# PCB1_v1.net
KiCad netlist of a schematic drawn in EAGLE
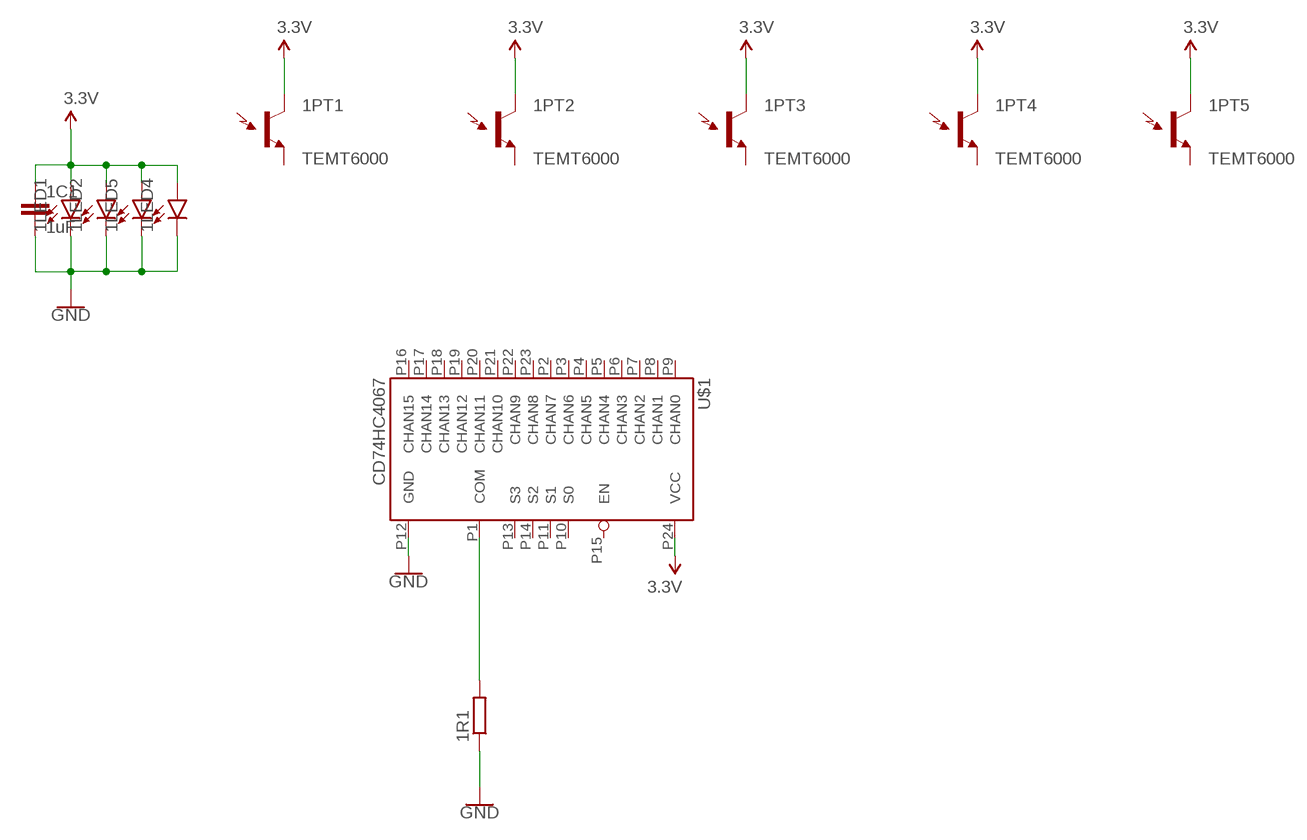
[diagram p0: schematic, sheet 1]
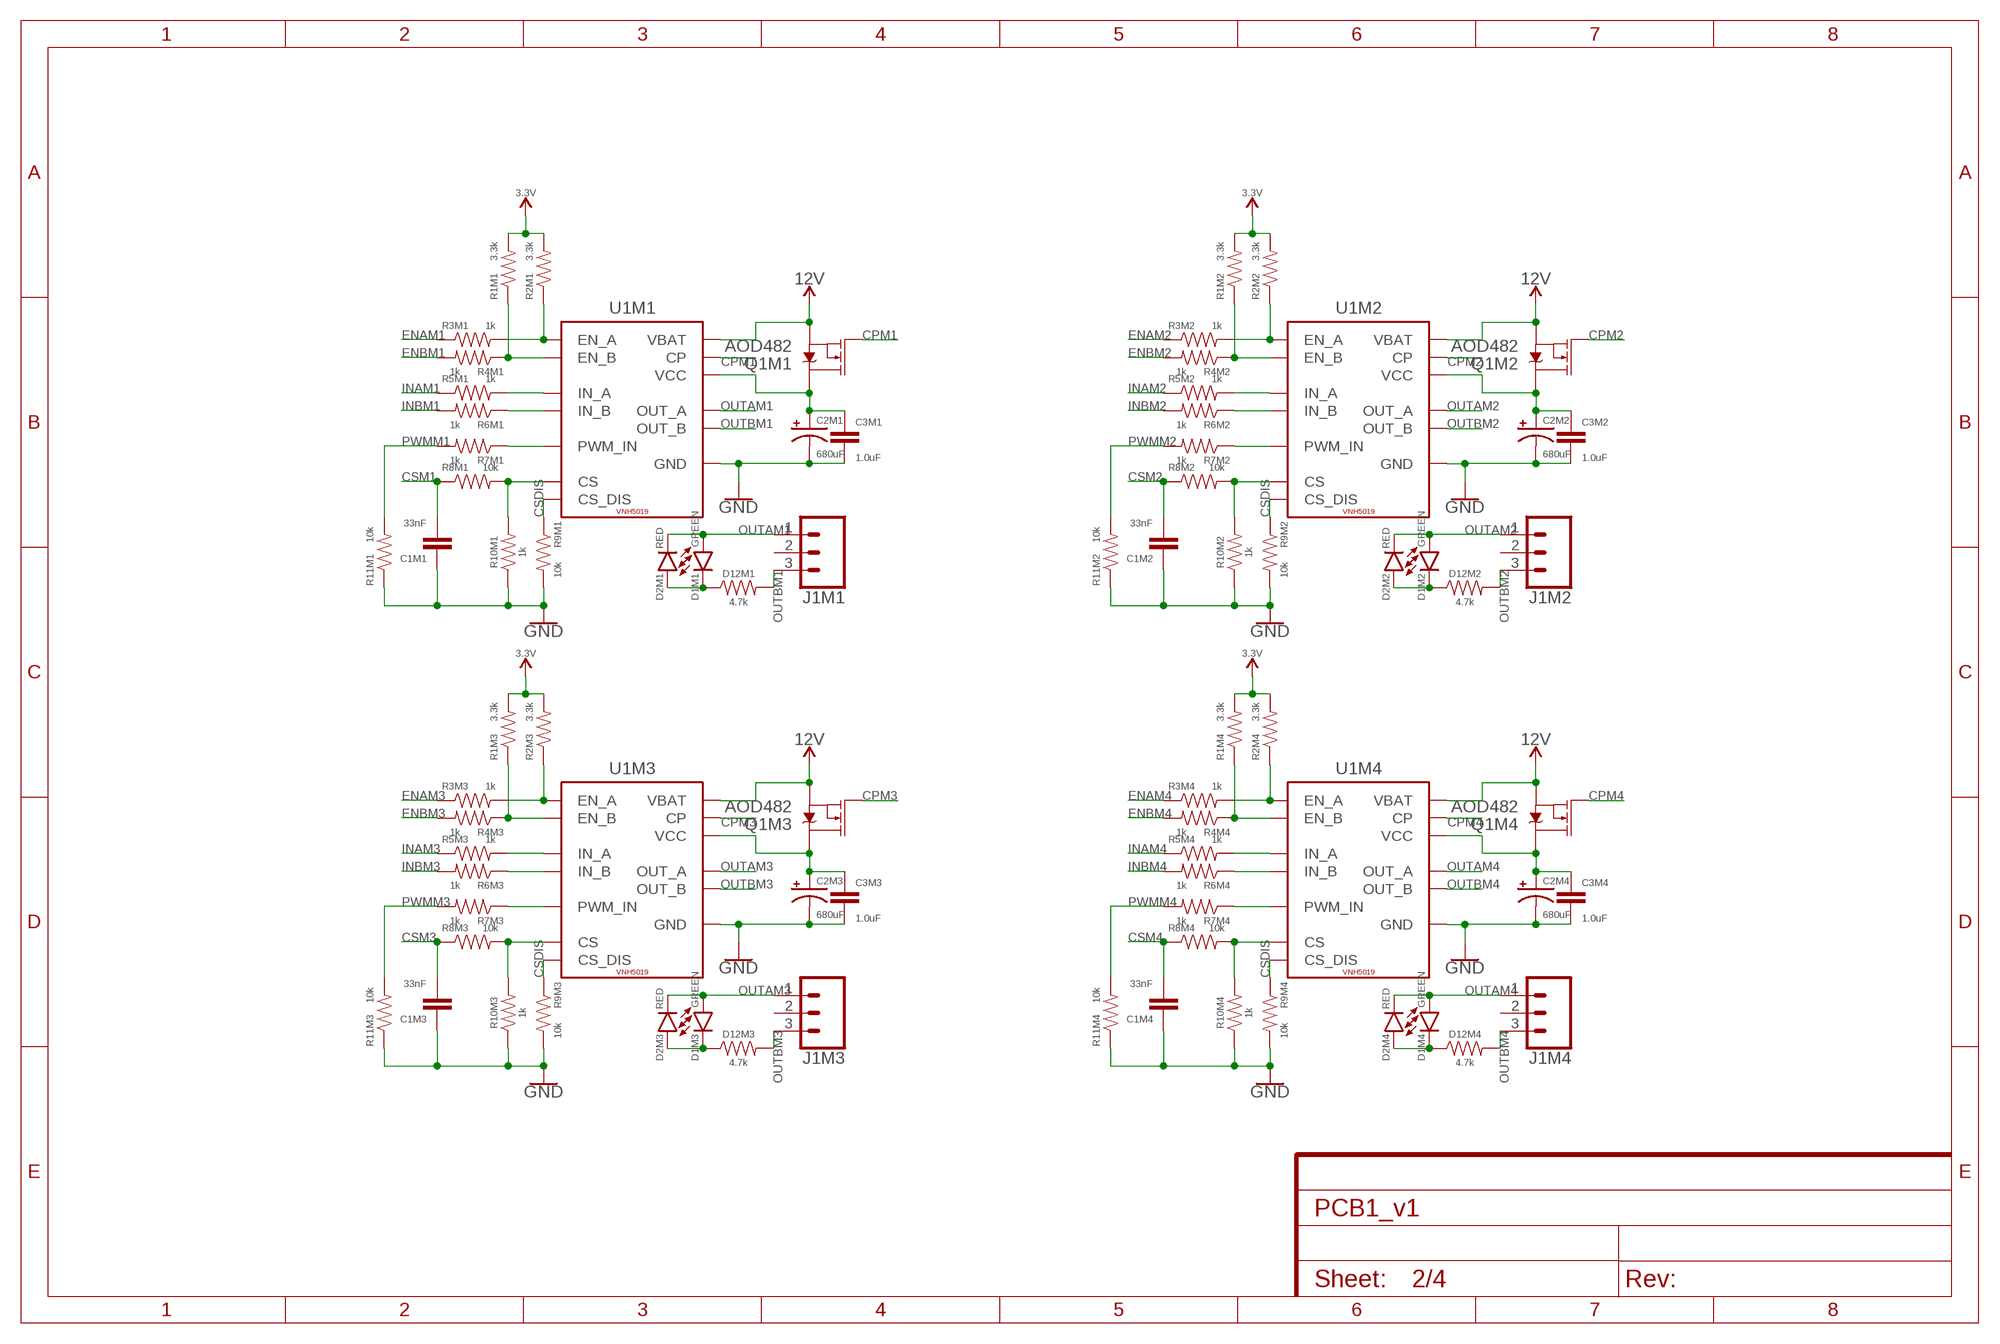
[diagram p1: schematic, sheet 2]
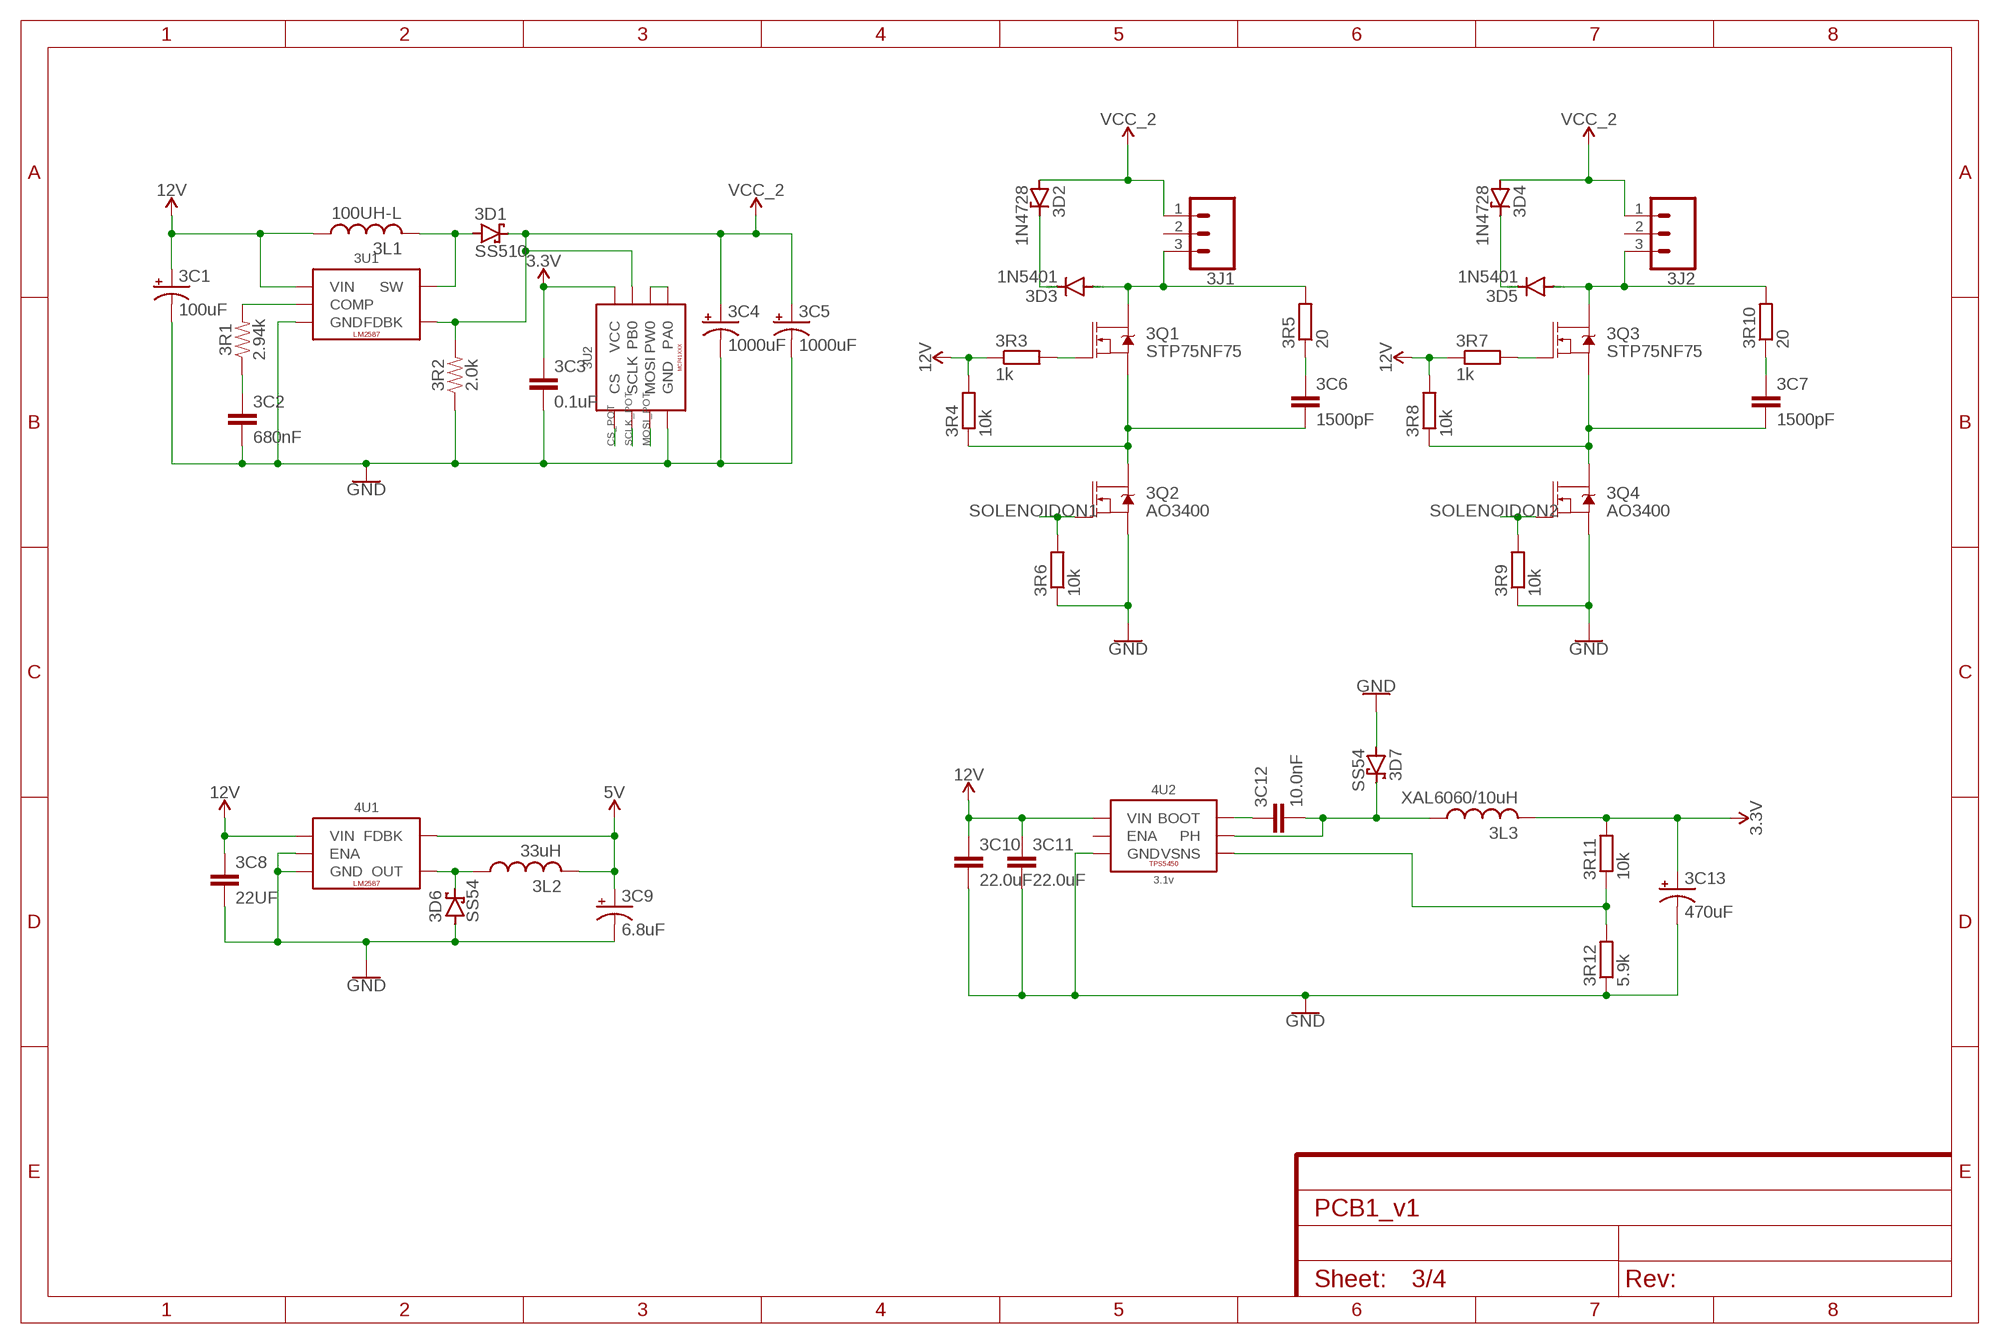
[diagram p2: schematic, sheet 3]
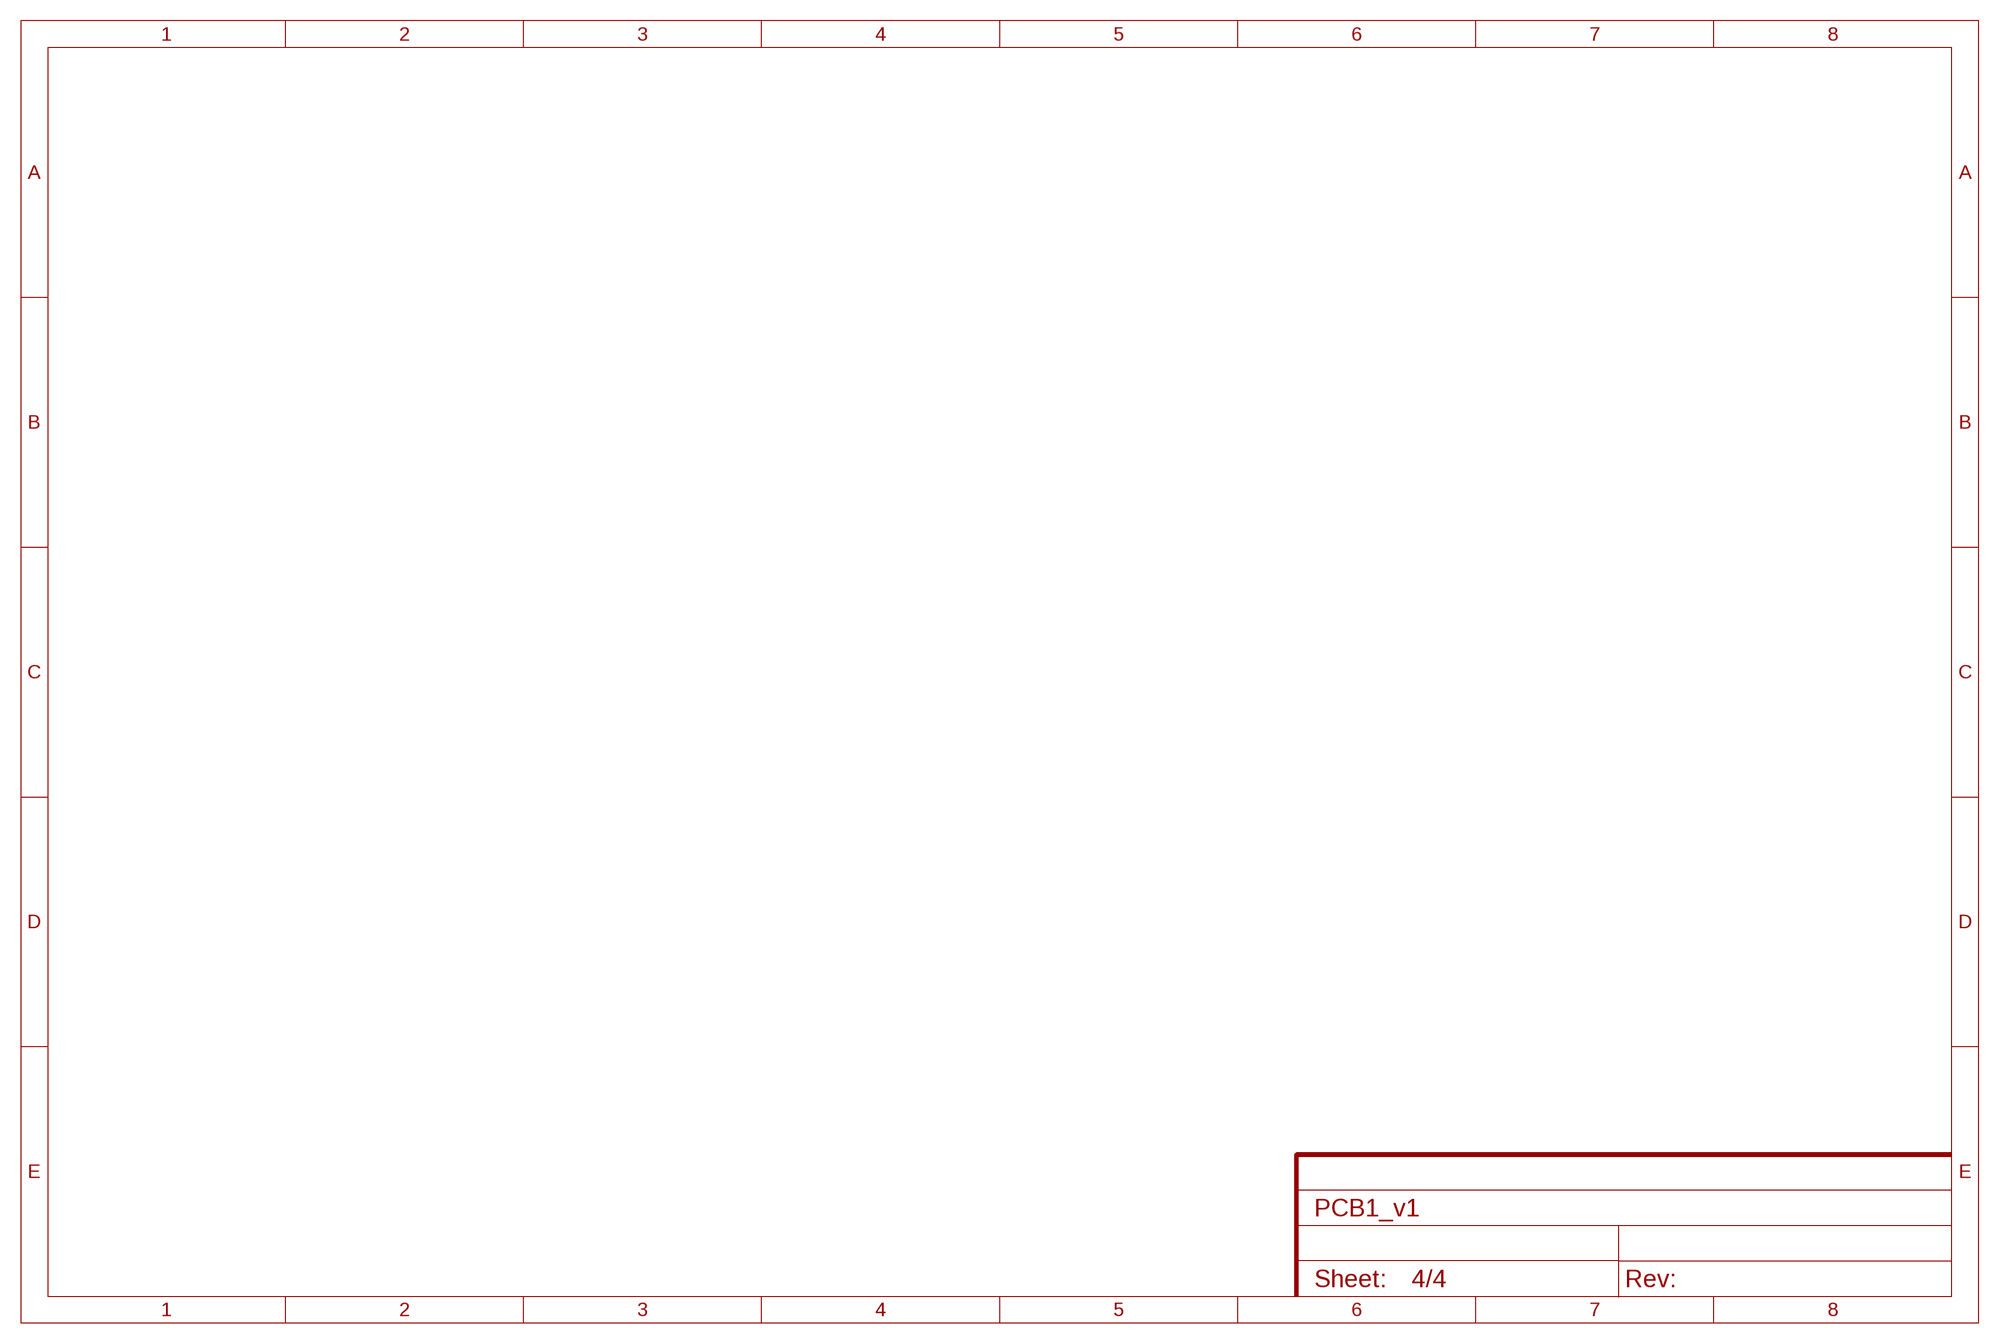
[diagram p3: schematic, sheet 4]

(export (version "E")
  (design (tool "Eeschema 10.0.6"))
  (components
    (comp (ref "3C1")
      (value "100uF")
      (footprint "eagle-import:PANASONIC_D")
      (libsource (lib "eagle-import") (part "100UF-POLAR-25V-20%(ELEC)"))
    )
    (comp (ref "3C2")
      (value "680nF")
      (footprint "eagle-import:0603")
      (libsource (lib "eagle-import") (part "680PF-0603-50V-10%"))
    )
    (comp (ref "3C3")
      (value "0.1uF")
      (footprint "eagle-import:0603")
      (libsource (lib "eagle-import") (part "0.1UF-0603-25V-5%"))
    )
    (comp (ref "3C4")
      (value "1000uF")
      (footprint "eagle-import:1000UF-CAP")
      (libsource (lib "eagle-import") (part "1000UF-CAP"))
    )
    (comp (ref "3C5")
      (value "1000uF")
      (footprint "eagle-import:1000UF-CAP")
      (libsource (lib "eagle-import") (part "1000UF-CAP"))
    )
    (comp (ref "3C6")
      (value "1500pF")
      (footprint "eagle-import:C0603")
      (libsource (lib "eagle-import") (part "C-EUC0603"))
    )
    (comp (ref "3C7")
      (value "1500pF")
      (footprint "eagle-import:C0603")
      (libsource (lib "eagle-import") (part "C-EUC0603"))
    )
    (comp (ref "3C8")
      (value "22UF")
      (footprint "eagle-import:1210")
      (libsource (lib "eagle-import") (part "22UF-1210-16V-20%"))
    )
    (comp (ref "3C9")
      (value "6.8uF")
      (footprint "eagle-import:A_3216-18R")
      (libsource (lib "eagle-import") (part "CPOL-USA/3216-18R"))
    )
    (comp (ref "3C10")
      (value "22.0uF")
      (footprint "eagle-import:C1210")
      (libsource (lib "eagle-import") (part "C-EUC1210"))
    )
    (comp (ref "3C11")
      (value "22.0uF")
      (footprint "eagle-import:C1210")
      (libsource (lib "eagle-import") (part "C-EUC1210"))
    )
    (comp (ref "3C12")
      (value "10.0nF")
      (footprint "eagle-import:C0603")
      (libsource (lib "eagle-import") (part "C-EUC0603"))
    )
    (comp (ref "3C13")
      (value "470uF")
      (footprint "eagle-import:D_7343-31R")
      (libsource (lib "eagle-import") (part "CPOL-USD/7343-31R"))
    )
    (comp (ref "3D1")
      (value "SS510")
      (footprint "eagle-import:SMB")
      (libsource (lib "eagle-import") (part "SCHOTTKY-DIODESMD"))
    )
    (comp (ref "3D2")
      (value "1N4728")
      (footprint "eagle-import:DO41Z10")
      (libsource (lib "eagle-import") (part "1N4728"))
    )
    (comp (ref "3D3")
      (value "1N5401")
      (footprint "eagle-import:DO201-15")
      (libsource (lib "eagle-import") (part "1N5400"))
    )
    (comp (ref "3D4")
      (value "1N4728")
      (footprint "eagle-import:DO41Z10")
      (libsource (lib "eagle-import") (part "1N4728"))
    )
    (comp (ref "3D5")
      (value "1N5401")
      (footprint "eagle-import:DO201-15")
      (libsource (lib "eagle-import") (part "1N5400"))
    )
    (comp (ref "3D6")
      (value "SS54")
      (footprint "eagle-import:SMB")
      (libsource (lib "eagle-import") (part "SCHOTTKY-DIODESMD"))
    )
    (comp (ref "3D7")
      (value "SS54")
      (footprint "eagle-import:SMB")
      (libsource (lib "eagle-import") (part "SCHOTTKY-DIODESMD"))
    )
    (comp (ref "3J1")
      (value "CONN_03-SCREW-5MM")
      (footprint "eagle-import:SCREWTERMINAL-5MM-3")
      (libsource (lib "eagle-import") (part "CONN_03-SCREW-5MM"))
    )
    (comp (ref "3J2")
      (value "CONN_03-SCREW-5MM")
      (footprint "eagle-import:SCREWTERMINAL-5MM-3")
      (libsource (lib "eagle-import") (part "CONN_03-SCREW-5MM"))
    )
    (comp (ref "3L1")
      (value "100UH-L")
      (footprint "eagle-import:100UH-L")
      (libsource (lib "eagle-import") (part "100UH-L"))
    )
    (comp (ref "3L2")
      (value "33uH")
      (footprint "eagle-import:127")
      (libsource (lib "eagle-import") (part "CDRH127"))
    )
    (comp (ref "3L3")
      (value "XAL6060/10uH")
      (footprint "eagle-import:XAL6060")
      (libsource (lib "eagle-import") (part "XAL6060"))
    )
    (comp (ref "3Q1")
      (value "STP75NF75")
      (footprint "eagle-import:TO220V")
      (libsource (lib "eagle-import") (part "MOSFET-NCH-FQP30N06L"))
    )
    (comp (ref "3Q2")
      (value "AO3400")
      (footprint "eagle-import:SOT23-3")
      (libsource (lib "eagle-import") (part "MOSFET-NCH-AO3404A"))
    )
    (comp (ref "3Q3")
      (value "STP75NF75")
      (footprint "eagle-import:TO220V")
      (libsource (lib "eagle-import") (part "MOSFET-NCH-FQP30N06L"))
    )
    (comp (ref "3Q4")
      (value "AO3400")
      (footprint "eagle-import:SOT23-3")
      (libsource (lib "eagle-import") (part "MOSFET-NCH-AO3404A"))
    )
    (comp (ref "3R1")
      (value "2.94k")
      (footprint "eagle-import:0603")
      (libsource (lib "eagle-import") (part "RESISTOR0603"))
    )
    (comp (ref "3R2")
      (value "2.0k")
      (footprint "eagle-import:0603")
      (libsource (lib "eagle-import") (part "2.0KOHM-0603-1/10W-5%"))
    )
    (comp (ref "3R3")
      (value "1k")
      (footprint "eagle-import:R0603")
      (libsource (lib "eagle-import") (part "R-EU_R0603"))
    )
    (comp (ref "3R4")
      (value "10k")
      (footprint "eagle-import:R0603")
      (libsource (lib "eagle-import") (part "R-EU_R0603"))
    )
    (comp (ref "3R5")
      (value "20")
      (footprint "eagle-import:R0603")
      (libsource (lib "eagle-import") (part "R-EU_R0603"))
    )
    (comp (ref "3R6")
      (value "10k")
      (footprint "eagle-import:R0603")
      (libsource (lib "eagle-import") (part "R-EU_R0603"))
    )
    (comp (ref "3R7")
      (value "1k")
      (footprint "eagle-import:R0603")
      (libsource (lib "eagle-import") (part "R-EU_R0603"))
    )
    (comp (ref "3R8")
      (value "10k")
      (footprint "eagle-import:R0603")
      (libsource (lib "eagle-import") (part "R-EU_R0603"))
    )
    (comp (ref "3R9")
      (value "10k")
      (footprint "eagle-import:R0603")
      (libsource (lib "eagle-import") (part "R-EU_R0603"))
    )
    (comp (ref "3R10")
      (value "20")
      (footprint "eagle-import:R0603")
      (libsource (lib "eagle-import") (part "R-EU_R0603"))
    )
    (comp (ref "3R11")
      (value "10k")
      (footprint "eagle-import:R0603")
      (libsource (lib "eagle-import") (part "R-EU_R0603"))
    )
    (comp (ref "3R12")
      (value "5.9k")
      (footprint "eagle-import:R0603")
      (libsource (lib "eagle-import") (part "R-EU_R0603"))
    )
    (comp (ref "3U1")
      (value "LM2587")
      (footprint "eagle-import:TO-263")
      (libsource (lib "eagle-import") (part "LM2587"))
    )
    (comp (ref "3U2")
      (value "MCP41XXX")
      (footprint "eagle-import:SOIC-8")
      (libsource (lib "eagle-import") (part "MCP41XXX"))
    )
    (comp (ref "4U1")
      (value "LM2596")
      (footprint "eagle-import:TO-263")
      (libsource (lib "eagle-import") (part "LM2596"))
    )
    (comp (ref "4U2")
      (value "3.1v")
      (footprint "eagle-import:POWERPAD-SOIC-8")
      (libsource (lib "eagle-import") (part "TPS5450"))
    )
    (comp (ref "1C1")
      (value "1uF")
      (footprint "eagle-import:C0603")
      (libsource (lib "eagle-import") (part "C-EUC0603"))
    )
    (comp (ref "1LED1")
      (value "3528LED")
      (footprint "eagle-import:3528")
      (libsource (lib "eagle-import") (part "3528LED"))
    )
    (comp (ref "1LED2")
      (value "3528LED")
      (footprint "eagle-import:3528")
      (libsource (lib "eagle-import") (part "3528LED"))
    )
    (comp (ref "1LED4")
      (value "3528LED")
      (footprint "eagle-import:3528")
      (libsource (lib "eagle-import") (part "3528LED"))
    )
    (comp (ref "1LED5")
      (value "3528LED")
      (footprint "eagle-import:3528")
      (libsource (lib "eagle-import") (part "3528LED"))
    )
    (comp (ref "1PT1")
      (value "TEMT6000")
      (footprint "eagle-import:TEMT6000")
      (libsource (lib "eagle-import") (part "LIGHT_SENSORTEMT6000"))
    )
    (comp (ref "1PT2")
      (value "TEMT6000")
      (footprint "eagle-import:TEMT6000")
      (libsource (lib "eagle-import") (part "LIGHT_SENSORTEMT6000"))
    )
    (comp (ref "1PT3")
      (value "TEMT6000")
      (footprint "eagle-import:TEMT6000")
      (libsource (lib "eagle-import") (part "LIGHT_SENSORTEMT6000"))
    )
    (comp (ref "1PT4")
      (value "TEMT6000")
      (footprint "eagle-import:TEMT6000")
      (libsource (lib "eagle-import") (part "LIGHT_SENSORTEMT6000"))
    )
    (comp (ref "1PT5")
      (value "TEMT6000")
      (footprint "eagle-import:TEMT6000")
      (libsource (lib "eagle-import") (part "LIGHT_SENSORTEMT6000"))
    )
    (comp (ref "1R1")
      (value "2k")
      (footprint "eagle-import:R0603")
      (libsource (lib "eagle-import") (part "R-EU_R0603"))
    )
    (comp (ref "U$1")
      (value "CD74HC4067")
      (footprint "eagle-import:SOIC-24")
      (libsource (lib "eagle-import") (part "CD74HC4067"))
    )
    (comp (ref "C1M1")
      (value "33nF")
      (footprint "eagle-import:0603")
      (libsource (lib "eagle-import") (part "33NF-0603-50V-10%"))
    )
    (comp (ref "C1M2")
      (value "33nF")
      (footprint "eagle-import:0603")
      (libsource (lib "eagle-import") (part "33NF-0603-50V-10%"))
    )
    (comp (ref "C1M3")
      (value "33nF")
      (footprint "eagle-import:0603")
      (libsource (lib "eagle-import") (part "33NF-0603-50V-10%"))
    )
    (comp (ref "C1M4")
      (value "33nF")
      (footprint "eagle-import:0603")
      (libsource (lib "eagle-import") (part "33NF-0603-50V-10%"))
    )
    (comp (ref "C2M1")
      (value "680uF")
      (footprint "eagle-import:E3,5-8")
      (libsource (lib "eagle-import") (part "CPOL-USE3.5-8"))
    )
    (comp (ref "C2M2")
      (value "680uF")
      (footprint "eagle-import:E3,5-8")
      (libsource (lib "eagle-import") (part "CPOL-USE3.5-8"))
    )
    (comp (ref "C2M3")
      (value "680uF")
      (footprint "eagle-import:E3,5-8")
      (libsource (lib "eagle-import") (part "CPOL-USE3.5-8"))
    )
    (comp (ref "C2M4")
      (value "680uF")
      (footprint "eagle-import:E3,5-8")
      (libsource (lib "eagle-import") (part "CPOL-USE3.5-8"))
    )
    (comp (ref "C3M1")
      (value "1.0uF")
      (footprint "eagle-import:0603")
      (libsource (lib "eagle-import") (part "1.0UF-0603-16V-10%-X7R"))
    )
    (comp (ref "C3M2")
      (value "1.0uF")
      (footprint "eagle-import:0603")
      (libsource (lib "eagle-import") (part "1.0UF-0603-16V-10%-X7R"))
    )
    (comp (ref "C3M3")
      (value "1.0uF")
      (footprint "eagle-import:0603")
      (libsource (lib "eagle-import") (part "1.0UF-0603-16V-10%-X7R"))
    )
    (comp (ref "C3M4")
      (value "1.0uF")
      (footprint "eagle-import:0603")
      (libsource (lib "eagle-import") (part "1.0UF-0603-16V-10%-X7R"))
    )
    (comp (ref "D1M1")
      (value "GREEN")
      (footprint "eagle-import:LED-1206")
      (libsource (lib "eagle-import") (part "LED-GREEN1206"))
    )
    (comp (ref "D1M2")
      (value "GREEN")
      (footprint "eagle-import:LED-1206")
      (libsource (lib "eagle-import") (part "LED-GREEN1206"))
    )
    (comp (ref "D1M3")
      (value "GREEN")
      (footprint "eagle-import:LED-1206")
      (libsource (lib "eagle-import") (part "LED-GREEN1206"))
    )
    (comp (ref "D1M4")
      (value "GREEN")
      (footprint "eagle-import:LED-1206")
      (libsource (lib "eagle-import") (part "LED-GREEN1206"))
    )
    (comp (ref "D2M1")
      (value "RED")
      (footprint "eagle-import:LED-1206")
      (libsource (lib "eagle-import") (part "LED-RED1206"))
    )
    (comp (ref "D2M2")
      (value "RED")
      (footprint "eagle-import:LED-1206")
      (libsource (lib "eagle-import") (part "LED-RED1206"))
    )
    (comp (ref "D2M3")
      (value "RED")
      (footprint "eagle-import:LED-1206")
      (libsource (lib "eagle-import") (part "LED-RED1206"))
    )
    (comp (ref "D2M4")
      (value "RED")
      (footprint "eagle-import:LED-1206")
      (libsource (lib "eagle-import") (part "LED-RED1206"))
    )
    (comp (ref "D12M1")
      (value "4.7k")
      (footprint "eagle-import:0603")
      (libsource (lib "eagle-import") (part "4.7KOHM-0603-1/10W-1%"))
    )
    (comp (ref "D12M2")
      (value "4.7k")
      (footprint "eagle-import:0603")
      (libsource (lib "eagle-import") (part "4.7KOHM-0603-1/10W-1%"))
    )
    (comp (ref "D12M3")
      (value "4.7k")
      (footprint "eagle-import:0603")
      (libsource (lib "eagle-import") (part "4.7KOHM-0603-1/10W-1%"))
    )
    (comp (ref "D12M4")
      (value "4.7k")
      (footprint "eagle-import:0603")
      (libsource (lib "eagle-import") (part "4.7KOHM-0603-1/10W-1%"))
    )
    (comp (ref "J1M1")
      (value "CONN_03-SCREW-5MM")
      (footprint "eagle-import:SCREWTERMINAL-5MM-3")
      (libsource (lib "eagle-import") (part "CONN_03-SCREW-5MM"))
    )
    (comp (ref "J1M2")
      (value "CONN_03-SCREW-5MM")
      (footprint "eagle-import:SCREWTERMINAL-5MM-3")
      (libsource (lib "eagle-import") (part "CONN_03-SCREW-5MM"))
    )
    (comp (ref "J1M3")
      (value "CONN_03-SCREW-5MM")
      (footprint "eagle-import:SCREWTERMINAL-5MM-3")
      (libsource (lib "eagle-import") (part "CONN_03-SCREW-5MM"))
    )
    (comp (ref "J1M4")
      (value "CONN_03-SCREW-5MM")
      (footprint "eagle-import:SCREWTERMINAL-5MM-3")
      (libsource (lib "eagle-import") (part "CONN_03-SCREW-5MM"))
    )
    (comp (ref "Q1M1")
      (value "AOD482")
      (footprint "eagle-import:DPAK")
      (libsource (lib "eagle-import") (part "MOSFET-NCH-FDD8780"))
    )
    (comp (ref "Q1M2")
      (value "AOD482")
      (footprint "eagle-import:DPAK")
      (libsource (lib "eagle-import") (part "MOSFET-NCH-FDD8780"))
    )
    (comp (ref "Q1M3")
      (value "AOD482")
      (footprint "eagle-import:DPAK")
      (libsource (lib "eagle-import") (part "MOSFET-NCH-FDD8780"))
    )
    (comp (ref "Q1M4")
      (value "AOD482")
      (footprint "eagle-import:DPAK")
      (libsource (lib "eagle-import") (part "MOSFET-NCH-FDD8780"))
    )
    (comp (ref "R1M1")
      (value "3.3k")
      (footprint "eagle-import:0603")
      (libsource (lib "eagle-import") (part "3.3KOHM-0603-1/10W-1%"))
    )
    (comp (ref "R1M2")
      (value "3.3k")
      (footprint "eagle-import:0603")
      (libsource (lib "eagle-import") (part "3.3KOHM-0603-1/10W-1%"))
    )
    (comp (ref "R1M3")
      (value "3.3k")
      (footprint "eagle-import:0603")
      (libsource (lib "eagle-import") (part "3.3KOHM-0603-1/10W-1%"))
    )
    (comp (ref "R1M4")
      (value "3.3k")
      (footprint "eagle-import:0603")
      (libsource (lib "eagle-import") (part "3.3KOHM-0603-1/10W-1%"))
    )
    (comp (ref "R2M1")
      (value "3.3k")
      (footprint "eagle-import:0603")
      (libsource (lib "eagle-import") (part "3.3KOHM-0603-1/10W-1%"))
    )
    (comp (ref "R2M2")
      (value "3.3k")
      (footprint "eagle-import:0603")
      (libsource (lib "eagle-import") (part "3.3KOHM-0603-1/10W-1%"))
    )
    (comp (ref "R2M3")
      (value "3.3k")
      (footprint "eagle-import:0603")
      (libsource (lib "eagle-import") (part "3.3KOHM-0603-1/10W-1%"))
    )
    (comp (ref "R2M4")
      (value "3.3k")
      (footprint "eagle-import:0603")
      (libsource (lib "eagle-import") (part "3.3KOHM-0603-1/10W-1%"))
    )
    (comp (ref "R3M1")
      (value "1k")
      (footprint "eagle-import:0603")
      (libsource (lib "eagle-import") (part "1KOHM-0603-1/10W-1%"))
    )
    (comp (ref "R3M2")
      (value "1k")
      (footprint "eagle-import:0603")
      (libsource (lib "eagle-import") (part "1KOHM-0603-1/10W-1%"))
    )
    (comp (ref "R3M3")
      (value "1k")
      (footprint "eagle-import:0603")
      (libsource (lib "eagle-import") (part "1KOHM-0603-1/10W-1%"))
    )
    (comp (ref "R3M4")
      (value "1k")
      (footprint "eagle-import:0603")
      (libsource (lib "eagle-import") (part "1KOHM-0603-1/10W-1%"))
    )
    (comp (ref "R4M1")
      (value "1k")
      (footprint "eagle-import:0603")
      (libsource (lib "eagle-import") (part "1KOHM-0603-1/10W-1%"))
    )
    (comp (ref "R4M2")
      (value "1k")
      (footprint "eagle-import:0603")
      (libsource (lib "eagle-import") (part "1KOHM-0603-1/10W-1%"))
    )
    (comp (ref "R4M3")
      (value "1k")
      (footprint "eagle-import:0603")
      (libsource (lib "eagle-import") (part "1KOHM-0603-1/10W-1%"))
    )
    (comp (ref "R4M4")
      (value "1k")
      (footprint "eagle-import:0603")
      (libsource (lib "eagle-import") (part "1KOHM-0603-1/10W-1%"))
    )
    (comp (ref "R5M1")
      (value "1k")
      (footprint "eagle-import:0603")
      (libsource (lib "eagle-import") (part "1KOHM-0603-1/10W-1%"))
    )
    (comp (ref "R5M2")
      (value "1k")
      (footprint "eagle-import:0603")
      (libsource (lib "eagle-import") (part "1KOHM-0603-1/10W-1%"))
    )
    (comp (ref "R5M3")
      (value "1k")
      (footprint "eagle-import:0603")
      (libsource (lib "eagle-import") (part "1KOHM-0603-1/10W-1%"))
    )
    (comp (ref "R5M4")
      (value "1k")
      (footprint "eagle-import:0603")
      (libsource (lib "eagle-import") (part "1KOHM-0603-1/10W-1%"))
    )
    (comp (ref "R6M1")
      (value "1k")
      (footprint "eagle-import:0603")
      (libsource (lib "eagle-import") (part "1KOHM-0603-1/10W-1%"))
    )
    (comp (ref "R6M2")
      (value "1k")
      (footprint "eagle-import:0603")
      (libsource (lib "eagle-import") (part "1KOHM-0603-1/10W-1%"))
    )
    (comp (ref "R6M3")
      (value "1k")
      (footprint "eagle-import:0603")
      (libsource (lib "eagle-import") (part "1KOHM-0603-1/10W-1%"))
    )
    (comp (ref "R6M4")
      (value "1k")
      (footprint "eagle-import:0603")
      (libsource (lib "eagle-import") (part "1KOHM-0603-1/10W-1%"))
    )
    (comp (ref "R7M1")
      (value "1k")
      (footprint "eagle-import:0603")
      (libsource (lib "eagle-import") (part "1KOHM-0603-1/10W-1%"))
    )
    (comp (ref "R7M2")
      (value "1k")
      (footprint "eagle-import:0603")
      (libsource (lib "eagle-import") (part "1KOHM-0603-1/10W-1%"))
    )
    (comp (ref "R7M3")
      (value "1k")
      (footprint "eagle-import:0603")
      (libsource (lib "eagle-import") (part "1KOHM-0603-1/10W-1%"))
    )
    (comp (ref "R7M4")
      (value "1k")
      (footprint "eagle-import:0603")
      (libsource (lib "eagle-import") (part "1KOHM-0603-1/10W-1%"))
    )
    (comp (ref "R8M1")
      (value "10k")
      (footprint "eagle-import:0603")
      (libsource (lib "eagle-import") (part "10KOHM-0603-1/10W-1%"))
    )
    (comp (ref "R8M2")
      (value "10k")
      (footprint "eagle-import:0603")
      (libsource (lib "eagle-import") (part "10KOHM-0603-1/10W-1%"))
    )
    (comp (ref "R8M3")
      (value "10k")
      (footprint "eagle-import:0603")
      (libsource (lib "eagle-import") (part "10KOHM-0603-1/10W-1%"))
    )
    (comp (ref "R8M4")
      (value "10k")
      (footprint "eagle-import:0603")
      (libsource (lib "eagle-import") (part "10KOHM-0603-1/10W-1%"))
    )
    (comp (ref "R9M1")
      (value "10k")
      (footprint "eagle-import:0603")
      (libsource (lib "eagle-import") (part "10KOHM-0603-1/10W-1%"))
    )
    (comp (ref "R9M2")
      (value "10k")
      (footprint "eagle-import:0603")
      (libsource (lib "eagle-import") (part "10KOHM-0603-1/10W-1%"))
    )
    (comp (ref "R9M3")
      (value "10k")
      (footprint "eagle-import:0603")
      (libsource (lib "eagle-import") (part "10KOHM-0603-1/10W-1%"))
    )
    (comp (ref "R9M4")
      (value "10k")
      (footprint "eagle-import:0603")
      (libsource (lib "eagle-import") (part "10KOHM-0603-1/10W-1%"))
    )
    (comp (ref "R10M1")
      (value "1k")
      (footprint "eagle-import:0603")
      (libsource (lib "eagle-import") (part "1KOHM-0603-1/10W-1%"))
    )
    (comp (ref "R10M2")
      (value "1k")
      (footprint "eagle-import:0603")
      (libsource (lib "eagle-import") (part "1KOHM-0603-1/10W-1%"))
    )
    (comp (ref "R10M3")
      (value "1k")
      (footprint "eagle-import:0603")
      (libsource (lib "eagle-import") (part "1KOHM-0603-1/10W-1%"))
    )
    (comp (ref "R10M4")
      (value "1k")
      (footprint "eagle-import:0603")
      (libsource (lib "eagle-import") (part "1KOHM-0603-1/10W-1%"))
    )
    (comp (ref "R11M1")
      (value "10k")
      (footprint "eagle-import:0603")
      (libsource (lib "eagle-import") (part "10KOHM-0603-1/10W-1%"))
    )
    (comp (ref "R11M2")
      (value "10k")
      (footprint "eagle-import:0603")
      (libsource (lib "eagle-import") (part "10KOHM-0603-1/10W-1%"))
    )
    (comp (ref "R11M3")
      (value "10k")
      (footprint "eagle-import:0603")
      (libsource (lib "eagle-import") (part "10KOHM-0603-1/10W-1%"))
    )
    (comp (ref "R11M4")
      (value "10k")
      (footprint "eagle-import:0603")
      (libsource (lib "eagle-import") (part "10KOHM-0603-1/10W-1%"))
    )
    (comp (ref "U1M1")
      (value "VNH5019")
      (footprint "eagle-import:POWERSO-30")
      (libsource (lib "eagle-import") (part "VNH5019"))
    )
    (comp (ref "U1M2")
      (value "VNH5019")
      (footprint "eagle-import:POWERSO-30")
      (libsource (lib "eagle-import") (part "VNH5019"))
    )
    (comp (ref "U1M3")
      (value "VNH5019")
      (footprint "eagle-import:POWERSO-30")
      (libsource (lib "eagle-import") (part "VNH5019"))
    )
    (comp (ref "U1M4")
      (value "VNH5019")
      (footprint "eagle-import:POWERSO-30")
      (libsource (lib "eagle-import") (part "VNH5019"))
    )
  )
  (nets
    (net (code "1") (name "3.3V") (class "Default")
      (node (ref "1C1") (pin "1") (pinfunction "1_1") (pintype "passive"))
      (node (ref "1LED1") (pin "A") (pinfunction "A_A") (pintype "passive"))
      (node (ref "1LED2") (pin "A") (pinfunction "A_A") (pintype "passive"))
      (node (ref "1LED4") (pin "A") (pinfunction "A_A") (pintype "passive"))
      (node (ref "1LED5") (pin "A") (pinfunction "A_A") (pintype "passive"))
      (node (ref "1PT1") (pin "COLLECTOR") (pinfunction "C1_COLLECTOR") (pintype "passive"))
      (node (ref "1PT2") (pin "COLLECTOR") (pinfunction "C1_COLLECTOR") (pintype "passive"))
      (node (ref "1PT3") (pin "COLLECTOR") (pinfunction "C1_COLLECTOR") (pintype "passive"))
      (node (ref "1PT4") (pin "COLLECTOR") (pinfunction "C1_COLLECTOR") (pintype "passive"))
      (node (ref "1PT5") (pin "COLLECTOR") (pinfunction "C1_COLLECTOR") (pintype "passive"))
      (node (ref "3C13") (pin "+") (pinfunction "+_+") (pintype "passive"))
      (node (ref "3C3") (pin "1") (pinfunction "1_1") (pintype "passive"))
      (node (ref "3L3") (pin "2") (pinfunction "2_2") (pintype "passive"))
      (node (ref "3R11") (pin "2") (pinfunction "2_2") (pintype "passive"))
      (node (ref "3U2") (pin "8") (pinfunction "VCC_8") (pintype "power_in"))
      (node (ref "R1M1") (pin "2") (pinfunction "2_2") (pintype "passive"))
      (node (ref "R1M2") (pin "2") (pinfunction "2_2") (pintype "passive"))
      (node (ref "R1M3") (pin "2") (pinfunction "2_2") (pintype "passive"))
      (node (ref "R1M4") (pin "2") (pinfunction "2_2") (pintype "passive"))
      (node (ref "R2M1") (pin "2") (pinfunction "2_2") (pintype "passive"))
      (node (ref "R2M2") (pin "2") (pinfunction "2_2") (pintype "passive"))
      (node (ref "R2M3") (pin "2") (pinfunction "2_2") (pintype "passive"))
      (node (ref "R2M4") (pin "2") (pinfunction "2_2") (pintype "passive"))
      (node (ref "U$1") (pin "P24") (pinfunction "VCC_P24") (pintype "bidirectional"))
    )
    (net (code "2") (name "5V") (class "Default")
      (node (ref "3C9") (pin "+") (pinfunction "+_+") (pintype "passive"))
      (node (ref "3L2") (pin "2") (pinfunction "2_2") (pintype "passive"))
      (node (ref "4U1") (pin "P4") (pinfunction "FDBK_P4") (pintype "output"))
    )
    (net (code "3") (name "12V") (class "Default")
      (node (ref "3C1") (pin "+") (pinfunction "+_+") (pintype "passive"))
      (node (ref "3C10") (pin "1") (pinfunction "1_1") (pintype "passive"))
      (node (ref "3C11") (pin "1") (pinfunction "1_1") (pintype "passive"))
      (node (ref "3C8") (pin "1") (pinfunction "1_1") (pintype "passive"))
      (node (ref "3L1") (pin "P1") (pinfunction "1_P1") (pintype "passive"))
      (node (ref "3R3") (pin "1") (pinfunction "1_1") (pintype "passive"))
      (node (ref "3R4") (pin "2") (pinfunction "2_2") (pintype "passive"))
      (node (ref "3R7") (pin "1") (pinfunction "1_1") (pintype "passive"))
      (node (ref "3R8") (pin "2") (pinfunction "2_2") (pintype "passive"))
      (node (ref "3U1") (pin "P5") (pinfunction "VIN_P5") (pintype "power_in"))
      (node (ref "4U1") (pin "P1") (pinfunction "VIN_P1") (pintype "power_in"))
      (node (ref "4U2") (pin "7") (pinfunction "VIN_7") (pintype "power_in"))
      (node (ref "Q1M1") (pin "3") (pinfunction "S_3") (pintype "bidirectional"))
      (node (ref "Q1M2") (pin "3") (pinfunction "S_3") (pintype "bidirectional"))
      (node (ref "Q1M3") (pin "3") (pinfunction "S_3") (pintype "bidirectional"))
      (node (ref "Q1M4") (pin "3") (pinfunction "S_3") (pintype "bidirectional"))
      (node (ref "U1M1") (pin "P12") (pinfunction "VBAT_P12") (pintype "power_in"))
      (node (ref "U1M2") (pin "P12") (pinfunction "VBAT_P12") (pintype "power_in"))
      (node (ref "U1M3") (pin "P12") (pinfunction "VBAT_P12") (pintype "power_in"))
      (node (ref "U1M4") (pin "P12") (pinfunction "VBAT_P12") (pintype "power_in"))
    )
    (net (code "4") (name "CPM1") (class "Default")
      (node (ref "Q1M1") (pin "1") (pinfunction "G_1") (pintype "bidirectional"))
      (node (ref "U1M1") (pin "P11") (pinfunction "CP_P11") (pintype "output"))
    )
    (net (code "5") (name "CPM2") (class "Default")
      (node (ref "Q1M2") (pin "1") (pinfunction "G_1") (pintype "bidirectional"))
      (node (ref "U1M2") (pin "P11") (pinfunction "CP_P11") (pintype "output"))
    )
    (net (code "6") (name "CPM3") (class "Default")
      (node (ref "Q1M3") (pin "1") (pinfunction "G_1") (pintype "bidirectional"))
      (node (ref "U1M3") (pin "P11") (pinfunction "CP_P11") (pintype "output"))
    )
    (net (code "7") (name "CPM4") (class "Default")
      (node (ref "Q1M4") (pin "1") (pinfunction "G_1") (pintype "bidirectional"))
      (node (ref "U1M4") (pin "P11") (pinfunction "CP_P11") (pintype "output"))
    )
    (net (code "8") (name "CSDIS") (class "Default")
      (node (ref "R9M1") (pin "1") (pinfunction "1_1") (pintype "passive"))
      (node (ref "R9M2") (pin "1") (pinfunction "1_1") (pintype "passive"))
      (node (ref "R9M3") (pin "1") (pinfunction "1_1") (pintype "passive"))
      (node (ref "R9M4") (pin "1") (pinfunction "1_1") (pintype "passive"))
      (node (ref "U1M1") (pin "P6") (pinfunction "CS_DIS_P6") (pintype "input"))
      (node (ref "U1M2") (pin "P6") (pinfunction "CS_DIS_P6") (pintype "input"))
      (node (ref "U1M3") (pin "P6") (pinfunction "CS_DIS_P6") (pintype "input"))
      (node (ref "U1M4") (pin "P6") (pinfunction "CS_DIS_P6") (pintype "input"))
    )
    (net (code "9") (name "CSM1") (class "Default")
      (node (ref "C1M1") (pin "2") (pinfunction "2_2") (pintype "passive"))
      (node (ref "R8M1") (pin "1") (pinfunction "1_1") (pintype "passive"))
    )
    (net (code "10") (name "CSM2") (class "Default")
      (node (ref "C1M2") (pin "2") (pinfunction "2_2") (pintype "passive"))
      (node (ref "R8M2") (pin "1") (pinfunction "1_1") (pintype "passive"))
    )
    (net (code "11") (name "CSM3") (class "Default")
      (node (ref "C1M3") (pin "2") (pinfunction "2_2") (pintype "passive"))
      (node (ref "R8M3") (pin "1") (pinfunction "1_1") (pintype "passive"))
    )
    (net (code "12") (name "CSM4") (class "Default")
      (node (ref "C1M4") (pin "2") (pinfunction "2_2") (pintype "passive"))
      (node (ref "R8M4") (pin "1") (pinfunction "1_1") (pintype "passive"))
    )
    (net (code "13") (name "CS_POT") (class "Default")
      (node (ref "3U2") (pin "1") (pinfunction "CS_1") (pintype "input"))
    )
    (net (code "14") (name "ENAM1") (class "Default")
      (node (ref "R3M1") (pin "1") (pinfunction "1_1") (pintype "passive"))
    )
    (net (code "15") (name "ENAM2") (class "Default")
      (node (ref "R3M2") (pin "1") (pinfunction "1_1") (pintype "passive"))
    )
    (net (code "16") (name "ENAM3") (class "Default")
      (node (ref "R3M3") (pin "1") (pinfunction "1_1") (pintype "passive"))
    )
    (net (code "17") (name "ENAM4") (class "Default")
      (node (ref "R3M4") (pin "1") (pinfunction "1_1") (pintype "passive"))
    )
    (net (code "18") (name "ENBM1") (class "Default")
      (node (ref "R4M1") (pin "2") (pinfunction "2_2") (pintype "passive"))
    )
    (net (code "19") (name "ENBM2") (class "Default")
      (node (ref "R4M2") (pin "2") (pinfunction "2_2") (pintype "passive"))
    )
    (net (code "20") (name "ENBM3") (class "Default")
      (node (ref "R4M3") (pin "2") (pinfunction "2_2") (pintype "passive"))
    )
    (net (code "21") (name "ENBM4") (class "Default")
      (node (ref "R4M4") (pin "2") (pinfunction "2_2") (pintype "passive"))
    )
    (net (code "22") (name "GND") (class "Default")
      (node (ref "1C1") (pin "2") (pinfunction "2_2") (pintype "passive"))
      (node (ref "1LED1") (pin "C") (pinfunction "C_C") (pintype "passive"))
      (node (ref "1LED2") (pin "C") (pinfunction "C_C") (pintype "passive"))
      (node (ref "1LED4") (pin "C") (pinfunction "C_C") (pintype "passive"))
      (node (ref "1LED5") (pin "C") (pinfunction "C_C") (pintype "passive"))
      (node (ref "1R1") (pin "1") (pinfunction "1_1") (pintype "passive"))
      (node (ref "3C1") (pin "-") (pinfunction "-_-") (pintype "passive"))
      (node (ref "3C10") (pin "2") (pinfunction "2_2") (pintype "passive"))
      (node (ref "3C11") (pin "2") (pinfunction "2_2") (pintype "passive"))
      (node (ref "3C13") (pin "-") (pinfunction "-_-") (pintype "passive"))
      (node (ref "3C2") (pin "2") (pinfunction "2_2") (pintype "passive"))
      (node (ref "3C3") (pin "2") (pinfunction "2_2") (pintype "passive"))
      (node (ref "3C4") (pin "-") (pinfunction "-_-") (pintype "passive"))
      (node (ref "3C5") (pin "-") (pinfunction "-_-") (pintype "passive"))
      (node (ref "3C8") (pin "2") (pinfunction "2_2") (pintype "passive"))
      (node (ref "3C9") (pin "-") (pinfunction "-_-") (pintype "passive"))
      (node (ref "3D6") (pin "A") (pinfunction "A_A") (pintype "passive"))
      (node (ref "3D7") (pin "A") (pinfunction "A_A") (pintype "passive"))
      (node (ref "3Q2") (pin "2") (pinfunction "S_2") (pintype "bidirectional"))
      (node (ref "3Q4") (pin "2") (pinfunction "S_2") (pintype "bidirectional"))
      (node (ref "3R12") (pin "1") (pinfunction "1_1") (pintype "passive"))
      (node (ref "3R2") (pin "1") (pinfunction "1_1") (pintype "passive"))
      (node (ref "3R6") (pin "1") (pinfunction "1_1") (pintype "passive"))
      (node (ref "3R9") (pin "1") (pinfunction "1_1") (pintype "passive"))
      (node (ref "3U1") (pin "P3") (pinfunction "GND_P3") (pintype "power_in"))
      (node (ref "3U2") (pin "4") (pinfunction "GND_4") (pintype "power_in"))
      (node (ref "4U1") (pin "P3") (pinfunction "GND_P3") (pintype "power_in"))
      (node (ref "4U1") (pin "P5") (pinfunction "ENA_P5") (pintype "bidirectional"))
      (node (ref "4U1") (pin "TAB") (pinfunction "GND_TAB") (pintype "power_in"))
      (node (ref "4U2") (pin "6") (pinfunction "GND_6") (pintype "power_in"))
      (node (ref "4U2") (pin "9") (pinfunction "GND_9") (pintype "power_in"))
      (node (ref "4U2") (pin "P$1") (pinfunction "GND_P$1") (pintype "power_in"))
      (node (ref "4U2") (pin "P$2") (pinfunction "GND_P$2") (pintype "power_in"))
      (node (ref "4U2") (pin "P$3") (pinfunction "GND_P$3") (pintype "power_in"))
      (node (ref "4U2") (pin "P$4") (pinfunction "GND_P$4") (pintype "power_in"))
      (node (ref "4U2") (pin "P$5") (pinfunction "GND_P$5") (pintype "power_in"))
      (node (ref "4U2") (pin "P$6") (pinfunction "GND_P$6") (pintype "power_in"))
      (node (ref "C1M1") (pin "1") (pinfunction "1_1") (pintype "passive"))
      (node (ref "C1M2") (pin "1") (pinfunction "1_1") (pintype "passive"))
      (node (ref "C1M3") (pin "1") (pinfunction "1_1") (pintype "passive"))
      (node (ref "C1M4") (pin "1") (pinfunction "1_1") (pintype "passive"))
      (node (ref "C2M1") (pin "-") (pinfunction "-_-") (pintype "passive"))
      (node (ref "C2M2") (pin "-") (pinfunction "-_-") (pintype "passive"))
      (node (ref "C2M3") (pin "-") (pinfunction "-_-") (pintype "passive"))
      (node (ref "C2M4") (pin "-") (pinfunction "-_-") (pintype "passive"))
      (node (ref "C3M1") (pin "2") (pinfunction "2_2") (pintype "passive"))
      (node (ref "C3M2") (pin "2") (pinfunction "2_2") (pintype "passive"))
      (node (ref "C3M3") (pin "2") (pinfunction "2_2") (pintype "passive"))
      (node (ref "C3M4") (pin "2") (pinfunction "2_2") (pintype "passive"))
      (node (ref "R10M1") (pin "1") (pinfunction "1_1") (pintype "passive"))
      (node (ref "R10M2") (pin "1") (pinfunction "1_1") (pintype "passive"))
      (node (ref "R10M3") (pin "1") (pinfunction "1_1") (pintype "passive"))
      (node (ref "R10M4") (pin "1") (pinfunction "1_1") (pintype "passive"))
      (node (ref "R11M1") (pin "1") (pinfunction "1_1") (pintype "passive"))
      (node (ref "R11M2") (pin "1") (pinfunction "1_1") (pintype "passive"))
      (node (ref "R11M3") (pin "1") (pinfunction "1_1") (pintype "passive"))
      (node (ref "R11M4") (pin "1") (pinfunction "1_1") (pintype "passive"))
      (node (ref "R9M1") (pin "2") (pinfunction "2_2") (pintype "passive"))
      (node (ref "R9M2") (pin "2") (pinfunction "2_2") (pintype "passive"))
      (node (ref "R9M3") (pin "2") (pinfunction "2_2") (pintype "passive"))
      (node (ref "R9M4") (pin "2") (pinfunction "2_2") (pintype "passive"))
      (node (ref "U$1") (pin "P12") (pinfunction "GND_P12") (pintype "bidirectional"))
      (node (ref "U1M1") (pin "P18") (pinfunction "GND_P18") (pintype "output"))
      (node (ref "U1M1") (pin "P19") (pinfunction "GND_P19") (pintype "output"))
      (node (ref "U1M1") (pin "P20") (pinfunction "GND_P20") (pintype "output"))
      (node (ref "U1M1") (pin "P26") (pinfunction "GND_P26") (pintype "output"))
      (node (ref "U1M1") (pin "P27") (pinfunction "GND_P27") (pintype "output"))
      (node (ref "U1M1") (pin "P28") (pinfunction "GND_P28") (pintype "output"))
      (node (ref "U1M2") (pin "P18") (pinfunction "GND_P18") (pintype "output"))
      (node (ref "U1M2") (pin "P19") (pinfunction "GND_P19") (pintype "output"))
      (node (ref "U1M2") (pin "P20") (pinfunction "GND_P20") (pintype "output"))
      (node (ref "U1M2") (pin "P26") (pinfunction "GND_P26") (pintype "output"))
      (node (ref "U1M2") (pin "P27") (pinfunction "GND_P27") (pintype "output"))
      (node (ref "U1M2") (pin "P28") (pinfunction "GND_P28") (pintype "output"))
      (node (ref "U1M3") (pin "P18") (pinfunction "GND_P18") (pintype "output"))
      (node (ref "U1M3") (pin "P19") (pinfunction "GND_P19") (pintype "output"))
      (node (ref "U1M3") (pin "P20") (pinfunction "GND_P20") (pintype "output"))
      (node (ref "U1M3") (pin "P26") (pinfunction "GND_P26") (pintype "output"))
      (node (ref "U1M3") (pin "P27") (pinfunction "GND_P27") (pintype "output"))
      (node (ref "U1M3") (pin "P28") (pinfunction "GND_P28") (pintype "output"))
      (node (ref "U1M4") (pin "P18") (pinfunction "GND_P18") (pintype "output"))
      (node (ref "U1M4") (pin "P19") (pinfunction "GND_P19") (pintype "output"))
      (node (ref "U1M4") (pin "P20") (pinfunction "GND_P20") (pintype "output"))
      (node (ref "U1M4") (pin "P26") (pinfunction "GND_P26") (pintype "output"))
      (node (ref "U1M4") (pin "P27") (pinfunction "GND_P27") (pintype "output"))
      (node (ref "U1M4") (pin "P28") (pinfunction "GND_P28") (pintype "output"))
    )
    (net (code "23") (name "INAM1") (class "Default")
      (node (ref "R5M1") (pin "1") (pinfunction "1_1") (pintype "passive"))
    )
    (net (code "24") (name "INAM2") (class "Default")
      (node (ref "R5M2") (pin "1") (pinfunction "1_1") (pintype "passive"))
    )
    (net (code "25") (name "INAM3") (class "Default")
      (node (ref "R5M3") (pin "1") (pinfunction "1_1") (pintype "passive"))
    )
    (net (code "26") (name "INAM4") (class "Default")
      (node (ref "R5M4") (pin "1") (pinfunction "1_1") (pintype "passive"))
    )
    (net (code "27") (name "INBM1") (class "Default")
      (node (ref "R6M1") (pin "2") (pinfunction "2_2") (pintype "passive"))
    )
    (net (code "28") (name "INBM2") (class "Default")
      (node (ref "R6M2") (pin "2") (pinfunction "2_2") (pintype "passive"))
    )
    (net (code "29") (name "INBM3") (class "Default")
      (node (ref "R6M3") (pin "2") (pinfunction "2_2") (pintype "passive"))
    )
    (net (code "30") (name "INBM4") (class "Default")
      (node (ref "R6M4") (pin "2") (pinfunction "2_2") (pintype "passive"))
    )
    (net (code "31") (name "MOSI_POT") (class "Default")
      (node (ref "3U2") (pin "3") (pinfunction "MOSI_3") (pintype "input"))
    )
    (net (code "32") (name "Net-(3C2-Pad1)") (class "Default")
      (node (ref "3C2") (pin "1") (pinfunction "1_1") (pintype "passive"))
      (node (ref "3R1") (pin "1") (pinfunction "1_1") (pintype "passive"))
    )
    (net (code "33") (name "Net-(3C6-Pad1)") (class "Default")
      (node (ref "3C6") (pin "1") (pinfunction "1_1") (pintype "passive"))
      (node (ref "3R5") (pin "1") (pinfunction "1_1") (pintype "passive"))
    )
    (net (code "34") (name "Net-(3C7-Pad1)") (class "Default")
      (node (ref "3C7") (pin "1") (pinfunction "1_1") (pintype "passive"))
      (node (ref "3R10") (pin "1") (pinfunction "1_1") (pintype "passive"))
    )
    (net (code "35") (name "Net-(3D2-PadC)") (class "Default")
      (node (ref "3D2") (pin "C") (pinfunction "C_C") (pintype "passive"))
      (node (ref "3D3") (pin "C") (pinfunction "C_C") (pintype "passive"))
    )
    (net (code "36") (name "Net-(3D4-PadC)") (class "Default")
      (node (ref "3D4") (pin "C") (pinfunction "C_C") (pintype "passive"))
      (node (ref "3D5") (pin "C") (pinfunction "C_C") (pintype "passive"))
    )
    (net (code "37") (name "Net-(3L1-2)") (class "Default")
      (node (ref "3D1") (pin "A") (pinfunction "A_A") (pintype "passive"))
      (node (ref "3L1") (pin "P2") (pinfunction "2_P2") (pintype "passive"))
      (node (ref "3U1") (pin "P4") (pinfunction "SW_P4") (pintype "output"))
    )
    (net (code "38") (name "Net-(3Q1-D)") (class "Default")
      (node (ref "3D3") (pin "A") (pinfunction "A_A") (pintype "passive"))
      (node (ref "3J1") (pin "3") (pinfunction "3_3") (pintype "passive"))
      (node (ref "3Q1") (pin "2") (pinfunction "D_2") (pintype "bidirectional"))
      (node (ref "3R5") (pin "2") (pinfunction "2_2") (pintype "passive"))
    )
    (net (code "39") (name "Net-(3Q1-G)") (class "Default")
      (node (ref "3Q1") (pin "1") (pinfunction "G_1") (pintype "bidirectional"))
      (node (ref "3R3") (pin "2") (pinfunction "2_2") (pintype "passive"))
    )
    (net (code "40") (name "Net-(3Q1-S)") (class "Default")
      (node (ref "3C6") (pin "2") (pinfunction "2_2") (pintype "passive"))
      (node (ref "3Q1") (pin "3") (pinfunction "S_3") (pintype "bidirectional"))
      (node (ref "3Q2") (pin "3") (pinfunction "D_3") (pintype "bidirectional"))
      (node (ref "3R4") (pin "1") (pinfunction "1_1") (pintype "passive"))
    )
    (net (code "41") (name "Net-(3Q3-D)") (class "Default")
      (node (ref "3D5") (pin "A") (pinfunction "A_A") (pintype "passive"))
      (node (ref "3J2") (pin "3") (pinfunction "3_3") (pintype "passive"))
      (node (ref "3Q3") (pin "2") (pinfunction "D_2") (pintype "bidirectional"))
      (node (ref "3R10") (pin "2") (pinfunction "2_2") (pintype "passive"))
    )
    (net (code "42") (name "Net-(3Q3-G)") (class "Default")
      (node (ref "3Q3") (pin "1") (pinfunction "G_1") (pintype "bidirectional"))
      (node (ref "3R7") (pin "2") (pinfunction "2_2") (pintype "passive"))
    )
    (net (code "43") (name "Net-(3Q3-S)") (class "Default")
      (node (ref "3C7") (pin "2") (pinfunction "2_2") (pintype "passive"))
      (node (ref "3Q3") (pin "3") (pinfunction "S_3") (pintype "bidirectional"))
      (node (ref "3Q4") (pin "3") (pinfunction "D_3") (pintype "bidirectional"))
      (node (ref "3R8") (pin "1") (pinfunction "1_1") (pintype "passive"))
    )
    (net (code "44") (name "Net-(3U1-COMP)") (class "Default")
      (node (ref "3R1") (pin "2") (pinfunction "2_2") (pintype "passive"))
      (node (ref "3U1") (pin "P1") (pinfunction "COMP_P1") (pintype "bidirectional"))
    )
    (net (code "45") (name "Net-(3U2-PA0)") (class "Default")
      (node (ref "3U2") (pin "5") (pinfunction "PA0_5") (pintype "bidirectional"))
      (node (ref "3U2") (pin "6") (pinfunction "PW0_6") (pintype "bidirectional"))
    )
    (net (code "46") (name "Net-(4U1-OUT)") (class "Default")
      (node (ref "3D6") (pin "C") (pinfunction "C_C") (pintype "passive"))
      (node (ref "3L2") (pin "1") (pinfunction "1_1") (pintype "passive"))
      (node (ref "4U1") (pin "P2") (pinfunction "OUT_P2") (pintype "input"))
    )
    (net (code "47") (name "Net-(4U2-BOOT)") (class "Default")
      (node (ref "3C12") (pin "1") (pinfunction "1_1") (pintype "passive"))
      (node (ref "4U2") (pin "1") (pinfunction "BOOT_1") (pintype "bidirectional"))
    )
    (net (code "48") (name "Net-(4U2-PH)") (class "Default")
      (node (ref "3C12") (pin "2") (pinfunction "2_2") (pintype "passive"))
      (node (ref "3D7") (pin "C") (pinfunction "C_C") (pintype "passive"))
      (node (ref "3L3") (pin "1") (pinfunction "1_1") (pintype "passive"))
      (node (ref "4U2") (pin "8") (pinfunction "PH_8") (pintype "bidirectional"))
    )
    (net (code "49") (name "Net-(4U2-VSNS)") (class "Default")
      (node (ref "3R11") (pin "1") (pinfunction "1_1") (pintype "passive"))
      (node (ref "3R12") (pin "2") (pinfunction "2_2") (pintype "passive"))
      (node (ref "4U2") (pin "4") (pinfunction "VSNS_4") (pintype "input"))
    )
    (net (code "50") (name "Net-(D12M1-Pad1)") (class "Default")
      (node (ref "D12M1") (pin "1") (pinfunction "1_1") (pintype "passive"))
      (node (ref "D1M1") (pin "C") (pinfunction "C_C") (pintype "passive"))
      (node (ref "D2M1") (pin "A") (pinfunction "A_A") (pintype "passive"))
    )
    (net (code "51") (name "Net-(D12M2-Pad1)") (class "Default")
      (node (ref "D12M2") (pin "1") (pinfunction "1_1") (pintype "passive"))
      (node (ref "D1M2") (pin "C") (pinfunction "C_C") (pintype "passive"))
      (node (ref "D2M2") (pin "A") (pinfunction "A_A") (pintype "passive"))
    )
    (net (code "52") (name "Net-(D12M3-Pad1)") (class "Default")
      (node (ref "D12M3") (pin "1") (pinfunction "1_1") (pintype "passive"))
      (node (ref "D1M3") (pin "C") (pinfunction "C_C") (pintype "passive"))
      (node (ref "D2M3") (pin "A") (pinfunction "A_A") (pintype "passive"))
    )
    (net (code "53") (name "Net-(D12M4-Pad1)") (class "Default")
      (node (ref "D12M4") (pin "1") (pinfunction "1_1") (pintype "passive"))
      (node (ref "D1M4") (pin "C") (pinfunction "C_C") (pintype "passive"))
      (node (ref "D2M4") (pin "A") (pinfunction "A_A") (pintype "passive"))
    )
    (net (code "54") (name "Net-(Q1M1-D)") (class "Default")
      (node (ref "C2M1") (pin "+") (pinfunction "+_+") (pintype "passive"))
      (node (ref "C3M1") (pin "1") (pinfunction "1_1") (pintype "passive"))
      (node (ref "Q1M1") (pin "4") (pinfunction "D_4") (pintype "bidirectional"))
      (node (ref "U1M1") (pin "P13") (pinfunction "VCC_P13") (pintype "power_in"))
      (node (ref "U1M1") (pin "P23") (pinfunction "VCC_P23") (pintype "power_in"))
      (node (ref "U1M1") (pin "P3") (pinfunction "VCC_P3") (pintype "power_in"))
      (node (ref "U1M1") (pin "SLUG1") (pinfunction "VCC_SLUG1") (pintype "power_in"))
    )
    (net (code "55") (name "Net-(Q1M2-D)") (class "Default")
      (node (ref "C2M2") (pin "+") (pinfunction "+_+") (pintype "passive"))
      (node (ref "C3M2") (pin "1") (pinfunction "1_1") (pintype "passive"))
      (node (ref "Q1M2") (pin "4") (pinfunction "D_4") (pintype "bidirectional"))
      (node (ref "U1M2") (pin "P13") (pinfunction "VCC_P13") (pintype "power_in"))
      (node (ref "U1M2") (pin "P23") (pinfunction "VCC_P23") (pintype "power_in"))
      (node (ref "U1M2") (pin "P3") (pinfunction "VCC_P3") (pintype "power_in"))
      (node (ref "U1M2") (pin "SLUG1") (pinfunction "VCC_SLUG1") (pintype "power_in"))
    )
    (net (code "56") (name "Net-(Q1M3-D)") (class "Default")
      (node (ref "C2M3") (pin "+") (pinfunction "+_+") (pintype "passive"))
      (node (ref "C3M3") (pin "1") (pinfunction "1_1") (pintype "passive"))
      (node (ref "Q1M3") (pin "4") (pinfunction "D_4") (pintype "bidirectional"))
      (node (ref "U1M3") (pin "P13") (pinfunction "VCC_P13") (pintype "power_in"))
      (node (ref "U1M3") (pin "P23") (pinfunction "VCC_P23") (pintype "power_in"))
      (node (ref "U1M3") (pin "P3") (pinfunction "VCC_P3") (pintype "power_in"))
      (node (ref "U1M3") (pin "SLUG1") (pinfunction "VCC_SLUG1") (pintype "power_in"))
    )
    (net (code "57") (name "Net-(Q1M4-D)") (class "Default")
      (node (ref "C2M4") (pin "+") (pinfunction "+_+") (pintype "passive"))
      (node (ref "C3M4") (pin "1") (pinfunction "1_1") (pintype "passive"))
      (node (ref "Q1M4") (pin "4") (pinfunction "D_4") (pintype "bidirectional"))
      (node (ref "U1M4") (pin "P13") (pinfunction "VCC_P13") (pintype "power_in"))
      (node (ref "U1M4") (pin "P23") (pinfunction "VCC_P23") (pintype "power_in"))
      (node (ref "U1M4") (pin "P3") (pinfunction "VCC_P3") (pintype "power_in"))
      (node (ref "U1M4") (pin "SLUG1") (pinfunction "VCC_SLUG1") (pintype "power_in"))
    )
    (net (code "58") (name "Net-(U$1-COM)") (class "Default")
      (node (ref "1R1") (pin "2") (pinfunction "2_2") (pintype "passive"))
      (node (ref "U$1") (pin "P1") (pinfunction "COM_P1") (pintype "bidirectional"))
    )
    (net (code "59") (name "Net-(U1M1-CS)") (class "Default")
      (node (ref "R10M1") (pin "2") (pinfunction "2_2") (pintype "passive"))
      (node (ref "R8M1") (pin "2") (pinfunction "2_2") (pintype "passive"))
      (node (ref "U1M1") (pin "P8") (pinfunction "CS_P8") (pintype "output"))
    )
    (net (code "60") (name "Net-(U1M1-EN_A)") (class "Default")
      (node (ref "R2M1") (pin "1") (pinfunction "1_1") (pintype "passive"))
      (node (ref "R3M1") (pin "2") (pinfunction "2_2") (pintype "passive"))
      (node (ref "U1M1") (pin "P5") (pinfunction "EN_A_P5") (pintype "bidirectional"))
    )
    (net (code "61") (name "Net-(U1M1-EN_B)") (class "Default")
      (node (ref "R1M1") (pin "1") (pinfunction "1_1") (pintype "passive"))
      (node (ref "R4M1") (pin "1") (pinfunction "1_1") (pintype "passive"))
      (node (ref "U1M1") (pin "P9") (pinfunction "EN_B_P9") (pintype "bidirectional"))
    )
    (net (code "62") (name "Net-(U1M1-IN_A)") (class "Default")
      (node (ref "R5M1") (pin "2") (pinfunction "2_2") (pintype "passive"))
      (node (ref "U1M1") (pin "P4") (pinfunction "IN_A_P4") (pintype "input"))
    )
    (net (code "63") (name "Net-(U1M1-IN_B)") (class "Default")
      (node (ref "R6M1") (pin "1") (pinfunction "1_1") (pintype "passive"))
      (node (ref "U1M1") (pin "P10") (pinfunction "IN_B_P10") (pintype "input"))
    )
    (net (code "64") (name "Net-(U1M1-PWM_IN)") (class "Default")
      (node (ref "R7M1") (pin "1") (pinfunction "1_1") (pintype "passive"))
      (node (ref "U1M1") (pin "P7") (pinfunction "PWM_IN_P7") (pintype "input"))
    )
    (net (code "65") (name "Net-(U1M2-CS)") (class "Default")
      (node (ref "R10M2") (pin "2") (pinfunction "2_2") (pintype "passive"))
      (node (ref "R8M2") (pin "2") (pinfunction "2_2") (pintype "passive"))
      (node (ref "U1M2") (pin "P8") (pinfunction "CS_P8") (pintype "output"))
    )
    (net (code "66") (name "Net-(U1M2-EN_A)") (class "Default")
      (node (ref "R2M2") (pin "1") (pinfunction "1_1") (pintype "passive"))
      (node (ref "R3M2") (pin "2") (pinfunction "2_2") (pintype "passive"))
      (node (ref "U1M2") (pin "P5") (pinfunction "EN_A_P5") (pintype "bidirectional"))
    )
    (net (code "67") (name "Net-(U1M2-EN_B)") (class "Default")
      (node (ref "R1M2") (pin "1") (pinfunction "1_1") (pintype "passive"))
      (node (ref "R4M2") (pin "1") (pinfunction "1_1") (pintype "passive"))
      (node (ref "U1M2") (pin "P9") (pinfunction "EN_B_P9") (pintype "bidirectional"))
    )
    (net (code "68") (name "Net-(U1M2-IN_A)") (class "Default")
      (node (ref "R5M2") (pin "2") (pinfunction "2_2") (pintype "passive"))
      (node (ref "U1M2") (pin "P4") (pinfunction "IN_A_P4") (pintype "input"))
    )
    (net (code "69") (name "Net-(U1M2-IN_B)") (class "Default")
      (node (ref "R6M2") (pin "1") (pinfunction "1_1") (pintype "passive"))
      (node (ref "U1M2") (pin "P10") (pinfunction "IN_B_P10") (pintype "input"))
    )
    (net (code "70") (name "Net-(U1M2-PWM_IN)") (class "Default")
      (node (ref "R7M2") (pin "1") (pinfunction "1_1") (pintype "passive"))
      (node (ref "U1M2") (pin "P7") (pinfunction "PWM_IN_P7") (pintype "input"))
    )
    (net (code "71") (name "Net-(U1M3-CS)") (class "Default")
      (node (ref "R10M3") (pin "2") (pinfunction "2_2") (pintype "passive"))
      (node (ref "R8M3") (pin "2") (pinfunction "2_2") (pintype "passive"))
      (node (ref "U1M3") (pin "P8") (pinfunction "CS_P8") (pintype "output"))
    )
    (net (code "72") (name "Net-(U1M3-EN_A)") (class "Default")
      (node (ref "R2M3") (pin "1") (pinfunction "1_1") (pintype "passive"))
      (node (ref "R3M3") (pin "2") (pinfunction "2_2") (pintype "passive"))
      (node (ref "U1M3") (pin "P5") (pinfunction "EN_A_P5") (pintype "bidirectional"))
    )
    (net (code "73") (name "Net-(U1M3-EN_B)") (class "Default")
      (node (ref "R1M3") (pin "1") (pinfunction "1_1") (pintype "passive"))
      (node (ref "R4M3") (pin "1") (pinfunction "1_1") (pintype "passive"))
      (node (ref "U1M3") (pin "P9") (pinfunction "EN_B_P9") (pintype "bidirectional"))
    )
    (net (code "74") (name "Net-(U1M3-IN_A)") (class "Default")
      (node (ref "R5M3") (pin "2") (pinfunction "2_2") (pintype "passive"))
      (node (ref "U1M3") (pin "P4") (pinfunction "IN_A_P4") (pintype "input"))
    )
    (net (code "75") (name "Net-(U1M3-IN_B)") (class "Default")
      (node (ref "R6M3") (pin "1") (pinfunction "1_1") (pintype "passive"))
      (node (ref "U1M3") (pin "P10") (pinfunction "IN_B_P10") (pintype "input"))
    )
    (net (code "76") (name "Net-(U1M3-PWM_IN)") (class "Default")
      (node (ref "R7M3") (pin "1") (pinfunction "1_1") (pintype "passive"))
      (node (ref "U1M3") (pin "P7") (pinfunction "PWM_IN_P7") (pintype "input"))
    )
    (net (code "77") (name "Net-(U1M4-CS)") (class "Default")
      (node (ref "R10M4") (pin "2") (pinfunction "2_2") (pintype "passive"))
      (node (ref "R8M4") (pin "2") (pinfunction "2_2") (pintype "passive"))
      (node (ref "U1M4") (pin "P8") (pinfunction "CS_P8") (pintype "output"))
    )
    (net (code "78") (name "Net-(U1M4-EN_A)") (class "Default")
      (node (ref "R2M4") (pin "1") (pinfunction "1_1") (pintype "passive"))
      (node (ref "R3M4") (pin "2") (pinfunction "2_2") (pintype "passive"))
      (node (ref "U1M4") (pin "P5") (pinfunction "EN_A_P5") (pintype "bidirectional"))
    )
    (net (code "79") (name "Net-(U1M4-EN_B)") (class "Default")
      (node (ref "R1M4") (pin "1") (pinfunction "1_1") (pintype "passive"))
      (node (ref "R4M4") (pin "1") (pinfunction "1_1") (pintype "passive"))
      (node (ref "U1M4") (pin "P9") (pinfunction "EN_B_P9") (pintype "bidirectional"))
    )
    (net (code "80") (name "Net-(U1M4-IN_A)") (class "Default")
      (node (ref "R5M4") (pin "2") (pinfunction "2_2") (pintype "passive"))
      (node (ref "U1M4") (pin "P4") (pinfunction "IN_A_P4") (pintype "input"))
    )
    (net (code "81") (name "Net-(U1M4-IN_B)") (class "Default")
      (node (ref "R6M4") (pin "1") (pinfunction "1_1") (pintype "passive"))
      (node (ref "U1M4") (pin "P10") (pinfunction "IN_B_P10") (pintype "input"))
    )
    (net (code "82") (name "Net-(U1M4-PWM_IN)") (class "Default")
      (node (ref "R7M4") (pin "1") (pinfunction "1_1") (pintype "passive"))
      (node (ref "U1M4") (pin "P7") (pinfunction "PWM_IN_P7") (pintype "input"))
    )
    (net (code "83") (name "OUTAM1") (class "Default")
      (node (ref "D1M1") (pin "A") (pinfunction "A_A") (pintype "passive"))
      (node (ref "D2M1") (pin "C") (pinfunction "C_C") (pintype "passive"))
      (node (ref "J1M1") (pin "1") (pinfunction "1_1") (pintype "passive"))
      (node (ref "U1M1") (pin "P1") (pinfunction "OUT_A_P1") (pintype "output"))
      (node (ref "U1M1") (pin "P25") (pinfunction "OUT_A_P25") (pintype "output"))
      (node (ref "U1M1") (pin "P30") (pinfunction "OUT_A_P30") (pintype "output"))
      (node (ref "U1M1") (pin "SLUG2") (pinfunction "OUT_A_SLUG2") (pintype "output"))
    )
    (net (code "84") (name "OUTAM2") (class "Default")
      (node (ref "D1M2") (pin "A") (pinfunction "A_A") (pintype "passive"))
      (node (ref "D2M2") (pin "C") (pinfunction "C_C") (pintype "passive"))
      (node (ref "J1M2") (pin "1") (pinfunction "1_1") (pintype "passive"))
      (node (ref "U1M2") (pin "P1") (pinfunction "OUT_A_P1") (pintype "output"))
      (node (ref "U1M2") (pin "P25") (pinfunction "OUT_A_P25") (pintype "output"))
      (node (ref "U1M2") (pin "P30") (pinfunction "OUT_A_P30") (pintype "output"))
      (node (ref "U1M2") (pin "SLUG2") (pinfunction "OUT_A_SLUG2") (pintype "output"))
    )
    (net (code "85") (name "OUTAM3") (class "Default")
      (node (ref "D1M3") (pin "A") (pinfunction "A_A") (pintype "passive"))
      (node (ref "D2M3") (pin "C") (pinfunction "C_C") (pintype "passive"))
      (node (ref "J1M3") (pin "1") (pinfunction "1_1") (pintype "passive"))
      (node (ref "U1M3") (pin "P1") (pinfunction "OUT_A_P1") (pintype "output"))
      (node (ref "U1M3") (pin "P25") (pinfunction "OUT_A_P25") (pintype "output"))
      (node (ref "U1M3") (pin "P30") (pinfunction "OUT_A_P30") (pintype "output"))
      (node (ref "U1M3") (pin "SLUG2") (pinfunction "OUT_A_SLUG2") (pintype "output"))
    )
    (net (code "86") (name "OUTAM4") (class "Default")
      (node (ref "D1M4") (pin "A") (pinfunction "A_A") (pintype "passive"))
      (node (ref "D2M4") (pin "C") (pinfunction "C_C") (pintype "passive"))
      (node (ref "J1M4") (pin "1") (pinfunction "1_1") (pintype "passive"))
      (node (ref "U1M4") (pin "P1") (pinfunction "OUT_A_P1") (pintype "output"))
      (node (ref "U1M4") (pin "P25") (pinfunction "OUT_A_P25") (pintype "output"))
      (node (ref "U1M4") (pin "P30") (pinfunction "OUT_A_P30") (pintype "output"))
      (node (ref "U1M4") (pin "SLUG2") (pinfunction "OUT_A_SLUG2") (pintype "output"))
    )
    (net (code "87") (name "OUTBM1") (class "Default")
      (node (ref "D12M1") (pin "2") (pinfunction "2_2") (pintype "passive"))
      (node (ref "J1M1") (pin "3") (pinfunction "3_3") (pintype "passive"))
      (node (ref "U1M1") (pin "P15") (pinfunction "OUT_B_P15") (pintype "output"))
      (node (ref "U1M1") (pin "P16") (pinfunction "OUT_B_P16") (pintype "output"))
      (node (ref "U1M1") (pin "P21") (pinfunction "OUT_B_P21") (pintype "output"))
      (node (ref "U1M1") (pin "SLUG3") (pinfunction "OUT_B_SLUG3") (pintype "output"))
    )
    (net (code "88") (name "OUTBM2") (class "Default")
      (node (ref "D12M2") (pin "2") (pinfunction "2_2") (pintype "passive"))
      (node (ref "J1M2") (pin "3") (pinfunction "3_3") (pintype "passive"))
      (node (ref "U1M2") (pin "P15") (pinfunction "OUT_B_P15") (pintype "output"))
      (node (ref "U1M2") (pin "P16") (pinfunction "OUT_B_P16") (pintype "output"))
      (node (ref "U1M2") (pin "P21") (pinfunction "OUT_B_P21") (pintype "output"))
      (node (ref "U1M2") (pin "SLUG3") (pinfunction "OUT_B_SLUG3") (pintype "output"))
    )
    (net (code "89") (name "OUTBM3") (class "Default")
      (node (ref "D12M3") (pin "2") (pinfunction "2_2") (pintype "passive"))
      (node (ref "J1M3") (pin "3") (pinfunction "3_3") (pintype "passive"))
      (node (ref "U1M3") (pin "P15") (pinfunction "OUT_B_P15") (pintype "output"))
      (node (ref "U1M3") (pin "P16") (pinfunction "OUT_B_P16") (pintype "output"))
      (node (ref "U1M3") (pin "P21") (pinfunction "OUT_B_P21") (pintype "output"))
      (node (ref "U1M3") (pin "SLUG3") (pinfunction "OUT_B_SLUG3") (pintype "output"))
    )
    (net (code "90") (name "OUTBM4") (class "Default")
      (node (ref "D12M4") (pin "2") (pinfunction "2_2") (pintype "passive"))
      (node (ref "J1M4") (pin "3") (pinfunction "3_3") (pintype "passive"))
      (node (ref "U1M4") (pin "P15") (pinfunction "OUT_B_P15") (pintype "output"))
      (node (ref "U1M4") (pin "P16") (pinfunction "OUT_B_P16") (pintype "output"))
      (node (ref "U1M4") (pin "P21") (pinfunction "OUT_B_P21") (pintype "output"))
      (node (ref "U1M4") (pin "SLUG3") (pinfunction "OUT_B_SLUG3") (pintype "output"))
    )
    (net (code "91") (name "PWMM1") (class "Default")
      (node (ref "R11M1") (pin "2") (pinfunction "2_2") (pintype "passive"))
      (node (ref "R7M1") (pin "2") (pinfunction "2_2") (pintype "passive"))
    )
    (net (code "92") (name "PWMM2") (class "Default")
      (node (ref "R11M2") (pin "2") (pinfunction "2_2") (pintype "passive"))
      (node (ref "R7M2") (pin "2") (pinfunction "2_2") (pintype "passive"))
    )
    (net (code "93") (name "PWMM3") (class "Default")
      (node (ref "R11M3") (pin "2") (pinfunction "2_2") (pintype "passive"))
      (node (ref "R7M3") (pin "2") (pinfunction "2_2") (pintype "passive"))
    )
    (net (code "94") (name "PWMM4") (class "Default")
      (node (ref "R11M4") (pin "2") (pinfunction "2_2") (pintype "passive"))
      (node (ref "R7M4") (pin "2") (pinfunction "2_2") (pintype "passive"))
    )
    (net (code "95") (name "SCLK_POT") (class "Default")
      (node (ref "3U2") (pin "2") (pinfunction "SCLK_2") (pintype "input"))
    )
    (net (code "96") (name "SOLENOIDON1") (class "Default")
      (node (ref "3Q2") (pin "1") (pinfunction "G_1") (pintype "bidirectional"))
      (node (ref "3R6") (pin "2") (pinfunction "2_2") (pintype "passive"))
    )
    (net (code "97") (name "SOLENOIDON2") (class "Default")
      (node (ref "3Q4") (pin "1") (pinfunction "G_1") (pintype "bidirectional"))
      (node (ref "3R9") (pin "2") (pinfunction "2_2") (pintype "passive"))
    )
    (net (code "98") (name "VCC_2") (class "Default")
      (node (ref "3C4") (pin "+") (pinfunction "+_+") (pintype "passive"))
      (node (ref "3C5") (pin "+") (pinfunction "+_+") (pintype "passive"))
      (node (ref "3D1") (pin "C") (pinfunction "C_C") (pintype "passive"))
      (node (ref "3D2") (pin "A") (pinfunction "A_A") (pintype "passive"))
      (node (ref "3D4") (pin "A") (pinfunction "A_A") (pintype "passive"))
      (node (ref "3J1") (pin "1") (pinfunction "1_1") (pintype "passive"))
      (node (ref "3J2") (pin "1") (pinfunction "1_1") (pintype "passive"))
      (node (ref "3R2") (pin "2") (pinfunction "2_2") (pintype "passive"))
      (node (ref "3U1") (pin "P2") (pinfunction "FDBK_P2") (pintype "input"))
      (node (ref "3U2") (pin "7") (pinfunction "PB0_7") (pintype "bidirectional"))
    )
    (net (code "99") (name "unconnected-(1PT1-E1-PadEMITTER)") (class "Default")
      (node (ref "1PT1") (pin "EMITTER") (pinfunction "E1_EMITTER") (pintype "passive"))
    )
    (net (code "100") (name "unconnected-(1PT2-E1-PadEMITTER)") (class "Default")
      (node (ref "1PT2") (pin "EMITTER") (pinfunction "E1_EMITTER") (pintype "passive"))
    )
    (net (code "101") (name "unconnected-(1PT3-E1-PadEMITTER)") (class "Default")
      (node (ref "1PT3") (pin "EMITTER") (pinfunction "E1_EMITTER") (pintype "passive"))
    )
    (net (code "102") (name "unconnected-(1PT4-E1-PadEMITTER)") (class "Default")
      (node (ref "1PT4") (pin "EMITTER") (pinfunction "E1_EMITTER") (pintype "passive"))
    )
    (net (code "103") (name "unconnected-(1PT5-E1-PadEMITTER)") (class "Default")
      (node (ref "1PT5") (pin "EMITTER") (pinfunction "E1_EMITTER") (pintype "passive"))
    )
    (net (code "104") (name "unconnected-(3J1-Pad2)") (class "Default")
      (node (ref "3J1") (pin "2") (pinfunction "2_2") (pintype "passive"))
    )
    (net (code "105") (name "unconnected-(3J2-Pad2)") (class "Default")
      (node (ref "3J2") (pin "2") (pinfunction "2_2") (pintype "passive"))
    )
    (net (code "106") (name "unconnected-(4U2-ENA-Pad5)") (class "Default")
      (node (ref "4U2") (pin "5") (pinfunction "ENA_5") (pintype "input"))
    )
    (net (code "107") (name "unconnected-(4U2-NC-Pad2)") (class "Default")
      (node (ref "4U2") (pin "2") (pinfunction "NC_2") (pintype "no_connect"))
    )
    (net (code "108") (name "unconnected-(4U2-NC-Pad3)") (class "Default")
      (node (ref "4U2") (pin "3") (pinfunction "NC_3") (pintype "no_connect"))
    )
    (net (code "109") (name "unconnected-(J1M1-Pad2)") (class "Default")
      (node (ref "J1M1") (pin "2") (pinfunction "2_2") (pintype "passive"))
    )
    (net (code "110") (name "unconnected-(J1M2-Pad2)") (class "Default")
      (node (ref "J1M2") (pin "2") (pinfunction "2_2") (pintype "passive"))
    )
    (net (code "111") (name "unconnected-(J1M3-Pad2)") (class "Default")
      (node (ref "J1M3") (pin "2") (pinfunction "2_2") (pintype "passive"))
    )
    (net (code "112") (name "unconnected-(J1M4-Pad2)") (class "Default")
      (node (ref "J1M4") (pin "2") (pinfunction "2_2") (pintype "passive"))
    )
    (net (code "113") (name "unconnected-(U$1-CHAN0-PadP9)") (class "Default")
      (node (ref "U$1") (pin "P9") (pinfunction "CHAN0_P9") (pintype "bidirectional"))
    )
    (net (code "114") (name "unconnected-(U$1-CHAN1-PadP8)") (class "Default")
      (node (ref "U$1") (pin "P8") (pinfunction "CHAN1_P8") (pintype "bidirectional"))
    )
    (net (code "115") (name "unconnected-(U$1-CHAN2-PadP7)") (class "Default")
      (node (ref "U$1") (pin "P7") (pinfunction "CHAN2_P7") (pintype "bidirectional"))
    )
    (net (code "116") (name "unconnected-(U$1-CHAN3-PadP6)") (class "Default")
      (node (ref "U$1") (pin "P6") (pinfunction "CHAN3_P6") (pintype "bidirectional"))
    )
    (net (code "117") (name "unconnected-(U$1-CHAN4-PadP5)") (class "Default")
      (node (ref "U$1") (pin "P5") (pinfunction "CHAN4_P5") (pintype "bidirectional"))
    )
    (net (code "118") (name "unconnected-(U$1-CHAN5-PadP4)") (class "Default")
      (node (ref "U$1") (pin "P4") (pinfunction "CHAN5_P4") (pintype "bidirectional"))
    )
    (net (code "119") (name "unconnected-(U$1-CHAN6-PadP3)") (class "Default")
      (node (ref "U$1") (pin "P3") (pinfunction "CHAN6_P3") (pintype "bidirectional"))
    )
    (net (code "120") (name "unconnected-(U$1-CHAN7-PadP2)") (class "Default")
      (node (ref "U$1") (pin "P2") (pinfunction "CHAN7_P2") (pintype "bidirectional"))
    )
    (net (code "121") (name "unconnected-(U$1-CHAN8-PadP23)") (class "Default")
      (node (ref "U$1") (pin "P23") (pinfunction "CHAN8_P23") (pintype "bidirectional"))
    )
    (net (code "122") (name "unconnected-(U$1-CHAN9-PadP22)") (class "Default")
      (node (ref "U$1") (pin "P22") (pinfunction "CHAN9_P22") (pintype "bidirectional"))
    )
    (net (code "123") (name "unconnected-(U$1-CHAN10-PadP21)") (class "Default")
      (node (ref "U$1") (pin "P21") (pinfunction "CHAN10_P21") (pintype "bidirectional"))
    )
    (net (code "124") (name "unconnected-(U$1-CHAN11-PadP20)") (class "Default")
      (node (ref "U$1") (pin "P20") (pinfunction "CHAN11_P20") (pintype "bidirectional"))
    )
    (net (code "125") (name "unconnected-(U$1-CHAN12-PadP19)") (class "Default")
      (node (ref "U$1") (pin "P19") (pinfunction "CHAN12_P19") (pintype "bidirectional"))
    )
    (net (code "126") (name "unconnected-(U$1-CHAN13-PadP18)") (class "Default")
      (node (ref "U$1") (pin "P18") (pinfunction "CHAN13_P18") (pintype "bidirectional"))
    )
    (net (code "127") (name "unconnected-(U$1-CHAN14-PadP17)") (class "Default")
      (node (ref "U$1") (pin "P17") (pinfunction "CHAN14_P17") (pintype "bidirectional"))
    )
    (net (code "128") (name "unconnected-(U$1-CHAN15-PadP16)") (class "Default")
      (node (ref "U$1") (pin "P16") (pinfunction "CHAN15_P16") (pintype "bidirectional"))
    )
    (net (code "129") (name "unconnected-(U$1-EN-PadP15)") (class "Default")
      (node (ref "U$1") (pin "P15") (pinfunction "EN_P15") (pintype "input"))
    )
    (net (code "130") (name "unconnected-(U$1-S0-PadP10)") (class "Default")
      (node (ref "U$1") (pin "P10") (pinfunction "S0_P10") (pintype "input"))
    )
    (net (code "131") (name "unconnected-(U$1-S1-PadP11)") (class "Default")
      (node (ref "U$1") (pin "P11") (pinfunction "S1_P11") (pintype "input"))
    )
    (net (code "132") (name "unconnected-(U$1-S2-PadP14)") (class "Default")
      (node (ref "U$1") (pin "P14") (pinfunction "S2_P14") (pintype "input"))
    )
    (net (code "133") (name "unconnected-(U$1-S3-PadP13)") (class "Default")
      (node (ref "U$1") (pin "P13") (pinfunction "S3_P13") (pintype "input"))
    )
    (net (code "134") (name "unconnected-(U1M1-NC-PadP2)") (class "Default")
      (node (ref "U1M1") (pin "P2") (pinfunction "NC_P2") (pintype "no_connect"))
    )
    (net (code "135") (name "unconnected-(U1M1-NC-PadP14)") (class "Default")
      (node (ref "U1M1") (pin "P14") (pinfunction "NC_P14") (pintype "no_connect"))
    )
    (net (code "136") (name "unconnected-(U1M1-NC-PadP17)") (class "Default")
      (node (ref "U1M1") (pin "P17") (pinfunction "NC_P17") (pintype "no_connect"))
    )
    (net (code "137") (name "unconnected-(U1M1-NC-PadP22)") (class "Default")
      (node (ref "U1M1") (pin "P22") (pinfunction "NC_P22") (pintype "no_connect"))
    )
    (net (code "138") (name "unconnected-(U1M1-NC-PadP24)") (class "Default")
      (node (ref "U1M1") (pin "P24") (pinfunction "NC_P24") (pintype "no_connect"))
    )
    (net (code "139") (name "unconnected-(U1M1-NC-PadP29)") (class "Default")
      (node (ref "U1M1") (pin "P29") (pinfunction "NC_P29") (pintype "no_connect"))
    )
    (net (code "140") (name "unconnected-(U1M2-NC-PadP2)") (class "Default")
      (node (ref "U1M2") (pin "P2") (pinfunction "NC_P2") (pintype "no_connect"))
    )
    (net (code "141") (name "unconnected-(U1M2-NC-PadP14)") (class "Default")
      (node (ref "U1M2") (pin "P14") (pinfunction "NC_P14") (pintype "no_connect"))
    )
    (net (code "142") (name "unconnected-(U1M2-NC-PadP17)") (class "Default")
      (node (ref "U1M2") (pin "P17") (pinfunction "NC_P17") (pintype "no_connect"))
    )
    (net (code "143") (name "unconnected-(U1M2-NC-PadP22)") (class "Default")
      (node (ref "U1M2") (pin "P22") (pinfunction "NC_P22") (pintype "no_connect"))
    )
    (net (code "144") (name "unconnected-(U1M2-NC-PadP24)") (class "Default")
      (node (ref "U1M2") (pin "P24") (pinfunction "NC_P24") (pintype "no_connect"))
    )
    (net (code "145") (name "unconnected-(U1M2-NC-PadP29)") (class "Default")
      (node (ref "U1M2") (pin "P29") (pinfunction "NC_P29") (pintype "no_connect"))
    )
    (net (code "146") (name "unconnected-(U1M3-NC-PadP2)") (class "Default")
      (node (ref "U1M3") (pin "P2") (pinfunction "NC_P2") (pintype "no_connect"))
    )
    (net (code "147") (name "unconnected-(U1M3-NC-PadP14)") (class "Default")
      (node (ref "U1M3") (pin "P14") (pinfunction "NC_P14") (pintype "no_connect"))
    )
    (net (code "148") (name "unconnected-(U1M3-NC-PadP17)") (class "Default")
      (node (ref "U1M3") (pin "P17") (pinfunction "NC_P17") (pintype "no_connect"))
    )
    (net (code "149") (name "unconnected-(U1M3-NC-PadP22)") (class "Default")
      (node (ref "U1M3") (pin "P22") (pinfunction "NC_P22") (pintype "no_connect"))
    )
    (net (code "150") (name "unconnected-(U1M3-NC-PadP24)") (class "Default")
      (node (ref "U1M3") (pin "P24") (pinfunction "NC_P24") (pintype "no_connect"))
    )
    (net (code "151") (name "unconnected-(U1M3-NC-PadP29)") (class "Default")
      (node (ref "U1M3") (pin "P29") (pinfunction "NC_P29") (pintype "no_connect"))
    )
    (net (code "152") (name "unconnected-(U1M4-NC-PadP2)") (class "Default")
      (node (ref "U1M4") (pin "P2") (pinfunction "NC_P2") (pintype "no_connect"))
    )
    (net (code "153") (name "unconnected-(U1M4-NC-PadP14)") (class "Default")
      (node (ref "U1M4") (pin "P14") (pinfunction "NC_P14") (pintype "no_connect"))
    )
    (net (code "154") (name "unconnected-(U1M4-NC-PadP17)") (class "Default")
      (node (ref "U1M4") (pin "P17") (pinfunction "NC_P17") (pintype "no_connect"))
    )
    (net (code "155") (name "unconnected-(U1M4-NC-PadP22)") (class "Default")
      (node (ref "U1M4") (pin "P22") (pinfunction "NC_P22") (pintype "no_connect"))
    )
    (net (code "156") (name "unconnected-(U1M4-NC-PadP24)") (class "Default")
      (node (ref "U1M4") (pin "P24") (pinfunction "NC_P24") (pintype "no_connect"))
    )
    (net (code "157") (name "unconnected-(U1M4-NC-PadP29)") (class "Default")
      (node (ref "U1M4") (pin "P29") (pinfunction "NC_P29") (pintype "no_connect"))
    )
  )
)
